# ThreePhaseMLI.net
KiCad netlist of a schematic drawn in Altium Designer
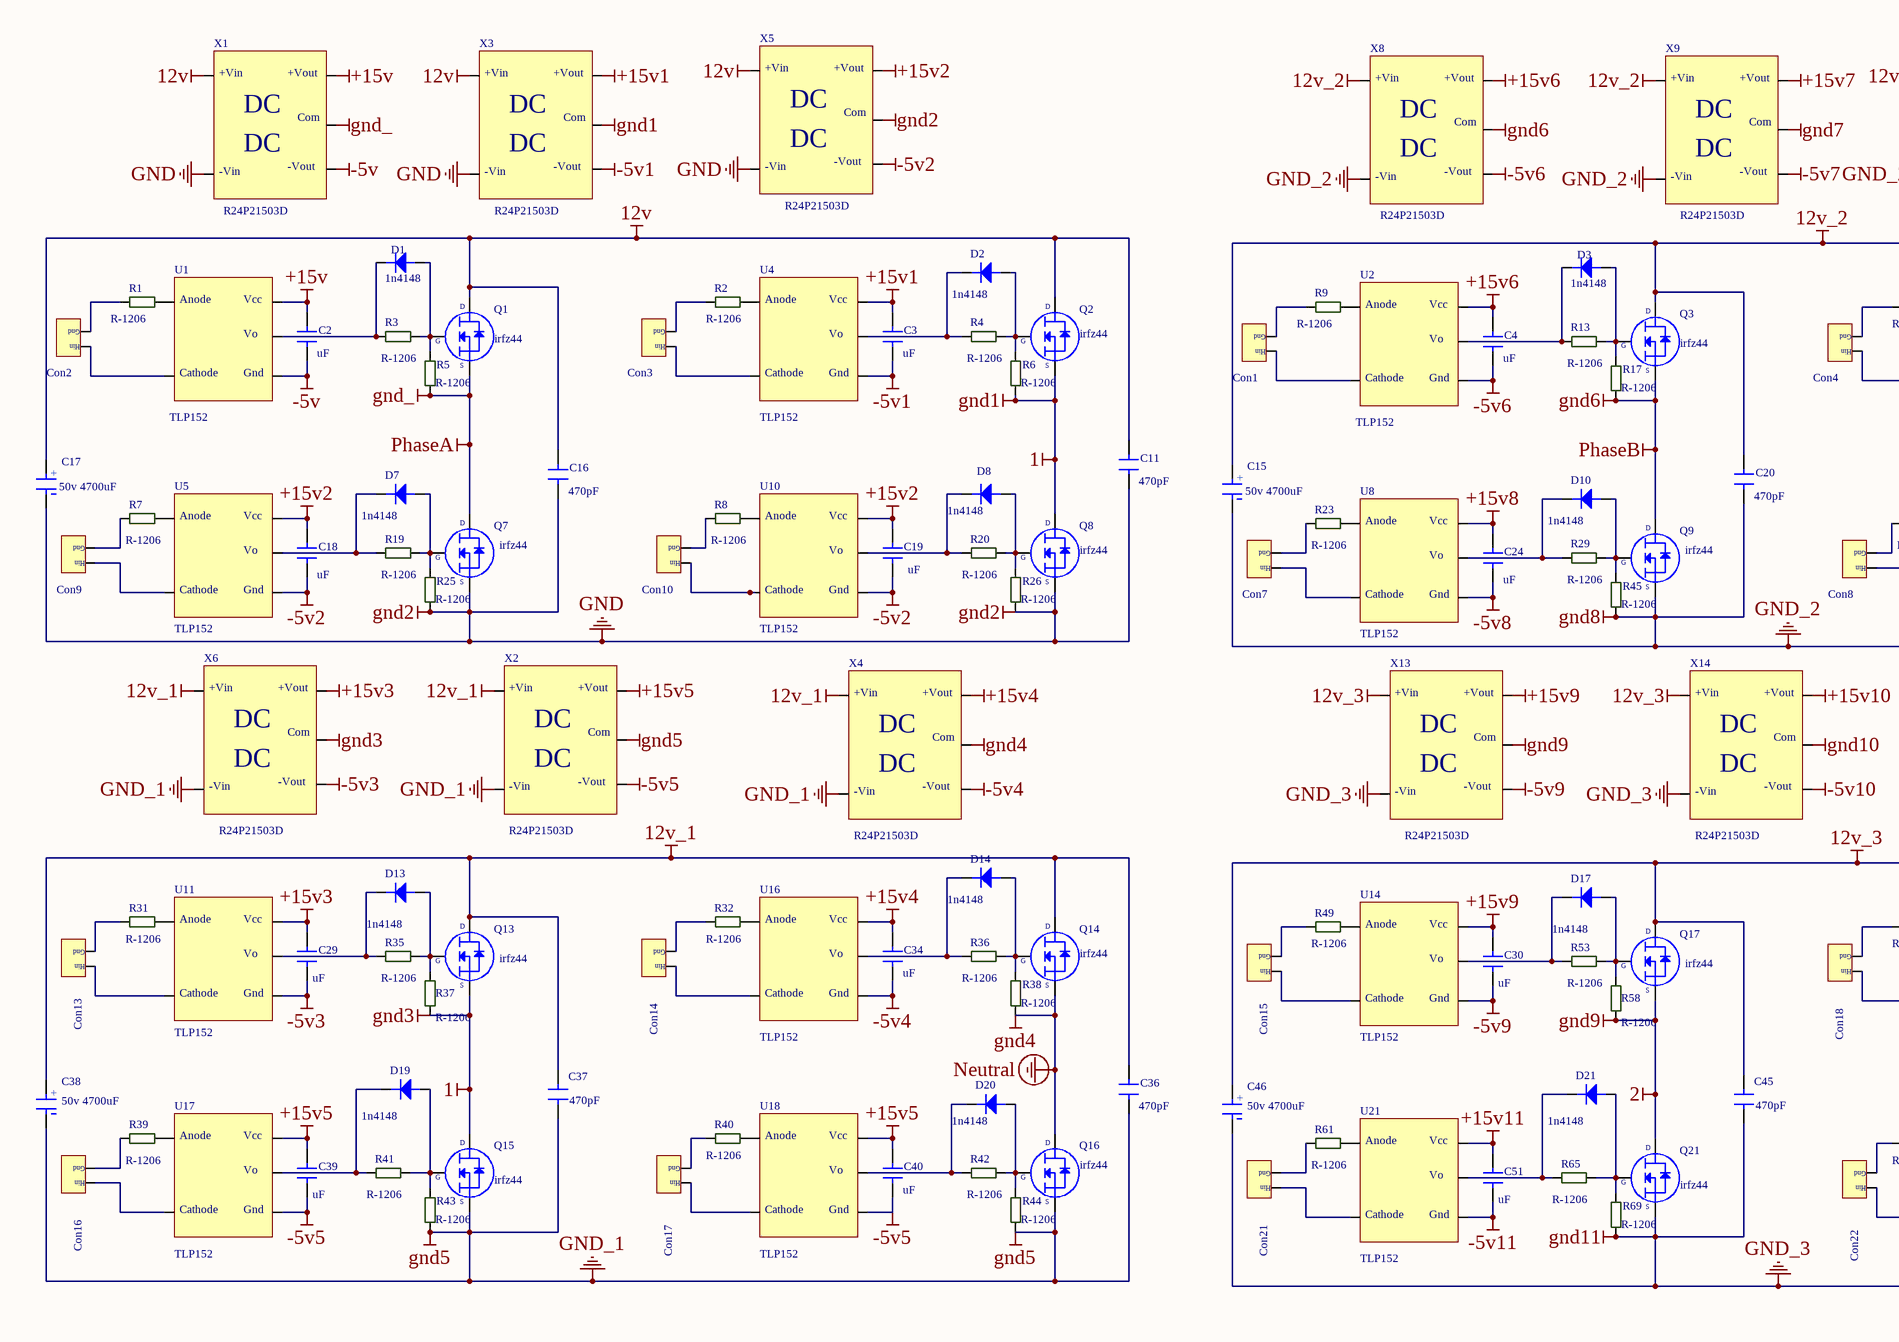
[diagram p0: ThreePhaseMLI.SchDoc, left]
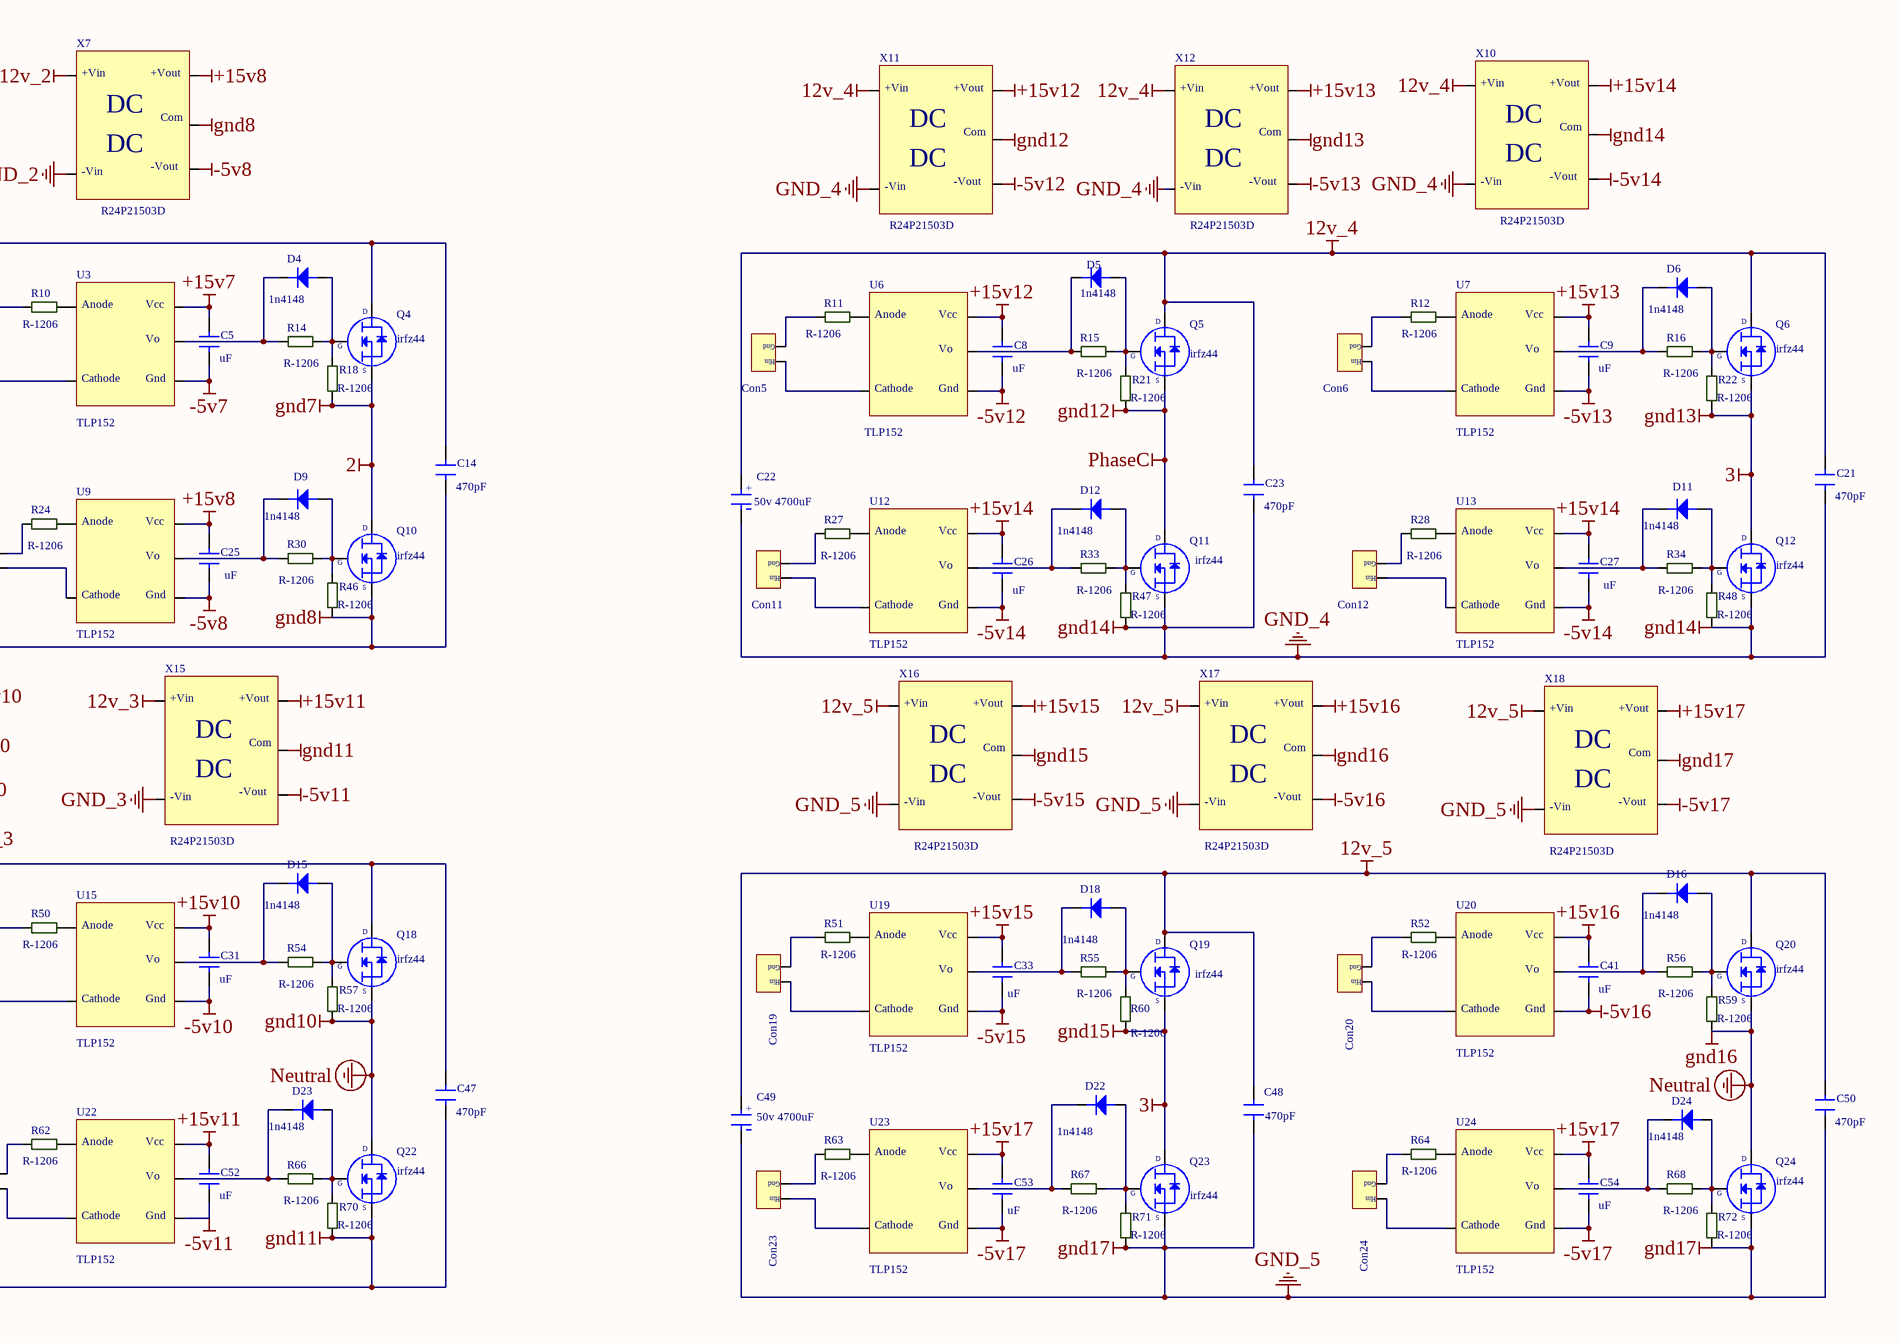
[diagram p1: ThreePhaseMLI.SchDoc, right]

(export (version "E")
  (design (tool "Eeschema 10.0.6"))
  (components
    (comp (ref "C2") (value "uF") (footprint "C-1206") (libsource (lib "ThreePhaseMLI") (part "C-1206")))
    (comp (ref "C3") (value "uF") (footprint "C-1206") (libsource (lib "ThreePhaseMLI") (part "C-1206")))
    (comp (ref "C4") (value "uF") (footprint "C-1206") (libsource (lib "ThreePhaseMLI") (part "C-1206")))
    (comp (ref "C5") (value "uF") (footprint "C-1206") (libsource (lib "ThreePhaseMLI") (part "C-1206")))
    (comp (ref "C8") (value "uF") (footprint "C-1206") (libsource (lib "ThreePhaseMLI") (part "C-1206")))
    (comp (ref "C9") (value "uF") (footprint "C-1206") (libsource (lib "ThreePhaseMLI") (part "C-1206")))
    (comp (ref "C11")
      (value "470pF")
      (footprint "100v 470pF")
      (libsource (lib "ThreePhaseMLI") (part "100v 470p cap"))
    )
    (comp (ref "C14")
      (value "470pF")
      (footprint "100v 470pF")
      (libsource (lib "ThreePhaseMLI") (part "100v 470p cap"))
    )
    (comp (ref "C15")
      (value "50v 4700uF")
      (footprint "63v 2200uF")
      (description "PKL5-063V472MM450 Aluminum Electrolytic Capacitors - Snap In 63volts 4700uF 20%")
      (fields
        (field (name "MANUFACTURER") "Nichicon")
        (field (name "MANUFACTURER PART NUMBER") "LKS1J472MESZ")
      )
      (libsource (lib "ThreePhaseMLI") (part "Aluminum Electrolytic Capacitors"))
    )
    (comp (ref "C16")
      (value "470pF")
      (footprint "100v 470pF")
      (libsource (lib "ThreePhaseMLI") (part "100v 470p cap"))
    )
    (comp (ref "C17")
      (value "50v 4700uF")
      (footprint "63v 2200uF")
      (description "PKL5-063V472MM450 Aluminum Electrolytic Capacitors - Snap In 63volts 4700uF 20%")
      (fields
        (field (name "MANUFACTURER") "Nichicon")
        (field (name "MANUFACTURER PART NUMBER") "LKS1J472MESZ")
      )
      (libsource (lib "ThreePhaseMLI") (part "Aluminum Electrolytic Capacitors"))
    )
    (comp (ref "C18") (value "uF") (footprint "C-1206") (libsource (lib "ThreePhaseMLI") (part "C-1206")))
    (comp (ref "C19") (value "uF") (footprint "C-1206") (libsource (lib "ThreePhaseMLI") (part "C-1206")))
    (comp (ref "C20")
      (value "470pF")
      (footprint "100v 470pF")
      (libsource (lib "ThreePhaseMLI") (part "100v 470p cap"))
    )
    (comp (ref "C21")
      (value "470pF")
      (footprint "100v 470pF")
      (libsource (lib "ThreePhaseMLI") (part "100v 470p cap"))
    )
    (comp (ref "C22")
      (value "50v 4700uF")
      (footprint "63v 2200uF")
      (description "PKL5-063V472MM450 Aluminum Electrolytic Capacitors - Snap In 63volts 4700uF 20%")
      (fields
        (field (name "MANUFACTURER") "Nichicon")
        (field (name "MANUFACTURER PART NUMBER") "LKS1J472MESZ")
      )
      (libsource (lib "ThreePhaseMLI") (part "Aluminum Electrolytic Capacitors"))
    )
    (comp (ref "C23")
      (value "470pF")
      (footprint "100v 470pF")
      (libsource (lib "ThreePhaseMLI") (part "100v 470p cap"))
    )
    (comp (ref "C24") (value "uF") (footprint "C-1206") (libsource (lib "ThreePhaseMLI") (part "C-1206")))
    (comp (ref "C25") (value "uF") (footprint "C-1206") (libsource (lib "ThreePhaseMLI") (part "C-1206")))
    (comp (ref "C26") (value "uF") (footprint "C-1206") (libsource (lib "ThreePhaseMLI") (part "C-1206")))
    (comp (ref "C27") (value "uF") (footprint "C-1206") (libsource (lib "ThreePhaseMLI") (part "C-1206")))
    (comp (ref "C29") (value "uF") (footprint "C-1206") (libsource (lib "ThreePhaseMLI") (part "C-1206")))
    (comp (ref "C30") (value "uF") (footprint "C-1206") (libsource (lib "ThreePhaseMLI") (part "C-1206")))
    (comp (ref "C31") (value "uF") (footprint "C-1206") (libsource (lib "ThreePhaseMLI") (part "C-1206")))
    (comp (ref "C33") (value "uF") (footprint "C-1206") (libsource (lib "ThreePhaseMLI") (part "C-1206")))
    (comp (ref "C34") (value "uF") (footprint "C-1206") (libsource (lib "ThreePhaseMLI") (part "C-1206")))
    (comp (ref "C36")
      (value "470pF")
      (footprint "100v 470pF")
      (libsource (lib "ThreePhaseMLI") (part "100v 470p cap"))
    )
    (comp (ref "C37")
      (value "470pF")
      (footprint "100v 470pF")
      (libsource (lib "ThreePhaseMLI") (part "100v 470p cap"))
    )
    (comp (ref "C38")
      (value "50v 4700uF")
      (footprint "63v 2200uF")
      (description "PKL5-063V472MM450 Aluminum Electrolytic Capacitors - Snap In 63volts 4700uF 20%")
      (fields
        (field (name "MANUFACTURER") "Nichicon")
        (field (name "MANUFACTURER PART NUMBER") "LKS1J472MESZ")
      )
      (libsource (lib "ThreePhaseMLI") (part "Aluminum Electrolytic Capacitors"))
    )
    (comp (ref "C39") (value "uF") (footprint "C-1206") (libsource (lib "ThreePhaseMLI") (part "C-1206")))
    (comp (ref "C40") (value "uF") (footprint "C-1206") (libsource (lib "ThreePhaseMLI") (part "C-1206")))
    (comp (ref "C41") (value "uF") (footprint "C-1206") (libsource (lib "ThreePhaseMLI") (part "C-1206")))
    (comp (ref "C45")
      (value "470pF")
      (footprint "100v 470pF")
      (libsource (lib "ThreePhaseMLI") (part "100v 470p cap"))
    )
    (comp (ref "C46")
      (value "50v 4700uF")
      (footprint "63v 2200uF")
      (description "PKL5-063V472MM450 Aluminum Electrolytic Capacitors - Snap In 63volts 4700uF 20%")
      (fields
        (field (name "MANUFACTURER") "Nichicon")
        (field (name "MANUFACTURER PART NUMBER") "LKS1J472MESZ")
      )
      (libsource (lib "ThreePhaseMLI") (part "Aluminum Electrolytic Capacitors"))
    )
    (comp (ref "C47")
      (value "470pF")
      (footprint "100v 470pF")
      (libsource (lib "ThreePhaseMLI") (part "100v 470p cap"))
    )
    (comp (ref "C48")
      (value "470pF")
      (footprint "100v 470pF")
      (libsource (lib "ThreePhaseMLI") (part "100v 470p cap"))
    )
    (comp (ref "C49")
      (value "50v 4700uF")
      (footprint "63v 2200uF")
      (description "PKL5-063V472MM450 Aluminum Electrolytic Capacitors - Snap In 63volts 4700uF 20%")
      (fields
        (field (name "MANUFACTURER") "Nichicon")
        (field (name "MANUFACTURER PART NUMBER") "LKS1J472MESZ")
      )
      (libsource (lib "ThreePhaseMLI") (part "Aluminum Electrolytic Capacitors"))
    )
    (comp (ref "C50")
      (value "470pF")
      (footprint "100v 470pF")
      (libsource (lib "ThreePhaseMLI") (part "100v 470p cap"))
    )
    (comp (ref "C51") (value "uF") (footprint "C-1206") (libsource (lib "ThreePhaseMLI") (part "C-1206")))
    (comp (ref "C52") (value "uF") (footprint "C-1206") (libsource (lib "ThreePhaseMLI") (part "C-1206")))
    (comp (ref "C53") (value "uF") (footprint "C-1206") (libsource (lib "ThreePhaseMLI") (part "C-1206")))
    (comp (ref "C54") (value "uF") (footprint "C-1206") (libsource (lib "ThreePhaseMLI") (part "C-1206")))
    (comp (ref "Con1")
      (value "Connector2")
      (footprint "Conn")
      (libsource (lib "ThreePhaseMLI") (part "Connector2"))
    )
    (comp (ref "Con2")
      (value "Connector2")
      (footprint "Conn")
      (libsource (lib "ThreePhaseMLI") (part "Connector2"))
    )
    (comp (ref "Con3")
      (value "Connector2")
      (footprint "Conn")
      (libsource (lib "ThreePhaseMLI") (part "Connector2"))
    )
    (comp (ref "Con4")
      (value "Connector2")
      (footprint "Conn")
      (libsource (lib "ThreePhaseMLI") (part "Connector2"))
    )
    (comp (ref "Con5")
      (value "Connector2")
      (footprint "Conn")
      (libsource (lib "ThreePhaseMLI") (part "Connector2"))
    )
    (comp (ref "Con6")
      (value "Connector2")
      (footprint "Conn")
      (libsource (lib "ThreePhaseMLI") (part "Connector2"))
    )
    (comp (ref "Con7")
      (value "Connector2")
      (footprint "Conn")
      (libsource (lib "ThreePhaseMLI") (part "Connector2"))
    )
    (comp (ref "Con8")
      (value "Connector2")
      (footprint "Conn")
      (libsource (lib "ThreePhaseMLI") (part "Connector2"))
    )
    (comp (ref "Con9")
      (value "Connector2")
      (footprint "Conn")
      (libsource (lib "ThreePhaseMLI") (part "Connector2"))
    )
    (comp (ref "Con10")
      (value "Connector2")
      (footprint "Conn")
      (libsource (lib "ThreePhaseMLI") (part "Connector2"))
    )
    (comp (ref "Con11")
      (value "Connector2")
      (footprint "Conn")
      (libsource (lib "ThreePhaseMLI") (part "Connector2"))
    )
    (comp (ref "Con12")
      (value "Connector2")
      (footprint "Conn")
      (libsource (lib "ThreePhaseMLI") (part "Connector2"))
    )
    (comp (ref "Con13")
      (value "Connector2")
      (footprint "Conn")
      (libsource (lib "ThreePhaseMLI") (part "Connector2"))
    )
    (comp (ref "Con14")
      (value "Connector2")
      (footprint "Conn")
      (libsource (lib "ThreePhaseMLI") (part "Connector2"))
    )
    (comp (ref "Con15")
      (value "Connector2")
      (footprint "Conn")
      (libsource (lib "ThreePhaseMLI") (part "Connector2"))
    )
    (comp (ref "Con16")
      (value "Connector2")
      (footprint "Conn")
      (libsource (lib "ThreePhaseMLI") (part "Connector2"))
    )
    (comp (ref "Con17")
      (value "Connector2")
      (footprint "Conn")
      (libsource (lib "ThreePhaseMLI") (part "Connector2"))
    )
    (comp (ref "Con18")
      (value "Connector2")
      (footprint "Conn")
      (libsource (lib "ThreePhaseMLI") (part "Connector2"))
    )
    (comp (ref "Con19")
      (value "Connector2")
      (footprint "Conn")
      (libsource (lib "ThreePhaseMLI") (part "Connector2"))
    )
    (comp (ref "Con20")
      (value "Connector2")
      (footprint "Conn")
      (libsource (lib "ThreePhaseMLI") (part "Connector2"))
    )
    (comp (ref "Con21")
      (value "Connector2")
      (footprint "Conn")
      (libsource (lib "ThreePhaseMLI") (part "Connector2"))
    )
    (comp (ref "Con22")
      (value "Connector2")
      (footprint "Conn")
      (libsource (lib "ThreePhaseMLI") (part "Connector2"))
    )
    (comp (ref "Con23")
      (value "Connector2")
      (footprint "Conn")
      (libsource (lib "ThreePhaseMLI") (part "Connector2"))
    )
    (comp (ref "Con24")
      (value "Connector2")
      (footprint "Conn")
      (libsource (lib "ThreePhaseMLI") (part "Connector2"))
    )
    (comp (ref "D1")
      (value "1n4148")
      (footprint "B5819")
      (description "Diode Small Signal Switching 100V 0.15A 2-Pin SOD-123 T/R")
      (fields
        (field (name "MANUFACTURER") "Vishay")
        (field (name "MANUFACTURER PART NUMBER") "1N4148W-E3-18")
      )
      (libsource (lib "ThreePhaseMLI") (part "1N4148W-E3-18"))
    )
    (comp (ref "D2")
      (value "1n4148")
      (footprint "B5819")
      (description "Diode Small Signal Switching 100V 0.15A 2-Pin SOD-123 T/R")
      (fields
        (field (name "MANUFACTURER") "Vishay")
        (field (name "MANUFACTURER PART NUMBER") "1N4148W-E3-18")
      )
      (libsource (lib "ThreePhaseMLI") (part "1N4148W-E3-18"))
    )
    (comp (ref "D3")
      (value "1n4148")
      (footprint "B5819")
      (description "Diode Small Signal Switching 100V 0.15A 2-Pin SOD-123 T/R")
      (fields
        (field (name "MANUFACTURER") "Vishay")
        (field (name "MANUFACTURER PART NUMBER") "1N4148W-E3-18")
      )
      (libsource (lib "ThreePhaseMLI") (part "1N4148W-E3-18"))
    )
    (comp (ref "D4")
      (value "1n4148")
      (footprint "B5819")
      (description "Diode Small Signal Switching 100V 0.15A 2-Pin SOD-123 T/R")
      (fields
        (field (name "MANUFACTURER") "Vishay")
        (field (name "MANUFACTURER PART NUMBER") "1N4148W-E3-18")
      )
      (libsource (lib "ThreePhaseMLI") (part "1N4148W-E3-18"))
    )
    (comp (ref "D5")
      (value "1n4148")
      (footprint "B5819")
      (description "Diode Small Signal Switching 100V 0.15A 2-Pin SOD-123 T/R")
      (fields
        (field (name "MANUFACTURER") "Vishay")
        (field (name "MANUFACTURER PART NUMBER") "1N4148W-E3-18")
      )
      (libsource (lib "ThreePhaseMLI") (part "1N4148W-E3-18"))
    )
    (comp (ref "D6")
      (value "1n4148")
      (footprint "B5819")
      (description "Diode Small Signal Switching 100V 0.15A 2-Pin SOD-123 T/R")
      (fields
        (field (name "MANUFACTURER") "Vishay")
        (field (name "MANUFACTURER PART NUMBER") "1N4148W-E3-18")
      )
      (libsource (lib "ThreePhaseMLI") (part "1N4148W-E3-18"))
    )
    (comp (ref "D7")
      (value "1n4148")
      (footprint "B5819")
      (description "Diode Small Signal Switching 100V 0.15A 2-Pin SOD-123 T/R")
      (fields
        (field (name "MANUFACTURER") "Vishay")
        (field (name "MANUFACTURER PART NUMBER") "1N4148W-E3-18")
      )
      (libsource (lib "ThreePhaseMLI") (part "1N4148W-E3-18"))
    )
    (comp (ref "D8")
      (value "1n4148")
      (footprint "B5819")
      (description "Diode Small Signal Switching 100V 0.15A 2-Pin SOD-123 T/R")
      (fields
        (field (name "MANUFACTURER") "Vishay")
        (field (name "MANUFACTURER PART NUMBER") "1N4148W-E3-18")
      )
      (libsource (lib "ThreePhaseMLI") (part "1N4148W-E3-18"))
    )
    (comp (ref "D9")
      (value "1n4148")
      (footprint "B5819")
      (description "Diode Small Signal Switching 100V 0.15A 2-Pin SOD-123 T/R")
      (fields
        (field (name "MANUFACTURER") "Vishay")
        (field (name "MANUFACTURER PART NUMBER") "1N4148W-E3-18")
      )
      (libsource (lib "ThreePhaseMLI") (part "1N4148W-E3-18"))
    )
    (comp (ref "D10")
      (value "1n4148")
      (footprint "B5819")
      (description "Diode Small Signal Switching 100V 0.15A 2-Pin SOD-123 T/R")
      (fields
        (field (name "MANUFACTURER") "Vishay")
        (field (name "MANUFACTURER PART NUMBER") "1N4148W-E3-18")
      )
      (libsource (lib "ThreePhaseMLI") (part "1N4148W-E3-18"))
    )
    (comp (ref "D11")
      (value "1n4148")
      (footprint "B5819")
      (description "Diode Small Signal Switching 100V 0.15A 2-Pin SOD-123 T/R")
      (fields
        (field (name "MANUFACTURER") "Vishay")
        (field (name "MANUFACTURER PART NUMBER") "1N4148W-E3-18")
      )
      (libsource (lib "ThreePhaseMLI") (part "1N4148W-E3-18"))
    )
    (comp (ref "D12")
      (value "1n4148")
      (footprint "B5819")
      (description "Diode Small Signal Switching 100V 0.15A 2-Pin SOD-123 T/R")
      (fields
        (field (name "MANUFACTURER") "Vishay")
        (field (name "MANUFACTURER PART NUMBER") "1N4148W-E3-18")
      )
      (libsource (lib "ThreePhaseMLI") (part "1N4148W-E3-18"))
    )
    (comp (ref "D13")
      (value "1n4148")
      (footprint "B5819")
      (description "Diode Small Signal Switching 100V 0.15A 2-Pin SOD-123 T/R")
      (fields
        (field (name "MANUFACTURER") "Vishay")
        (field (name "MANUFACTURER PART NUMBER") "1N4148W-E3-18")
      )
      (libsource (lib "ThreePhaseMLI") (part "1N4148W-E3-18"))
    )
    (comp (ref "D14")
      (value "1n4148")
      (footprint "B5819")
      (description "Diode Small Signal Switching 100V 0.15A 2-Pin SOD-123 T/R")
      (fields
        (field (name "MANUFACTURER") "Vishay")
        (field (name "MANUFACTURER PART NUMBER") "1N4148W-E3-18")
      )
      (libsource (lib "ThreePhaseMLI") (part "1N4148W-E3-18"))
    )
    (comp (ref "D15")
      (value "1n4148")
      (footprint "B5819")
      (description "Diode Small Signal Switching 100V 0.15A 2-Pin SOD-123 T/R")
      (fields
        (field (name "MANUFACTURER") "Vishay")
        (field (name "MANUFACTURER PART NUMBER") "1N4148W-E3-18")
      )
      (libsource (lib "ThreePhaseMLI") (part "1N4148W-E3-18"))
    )
    (comp (ref "D16")
      (value "1n4148")
      (footprint "B5819")
      (description "Diode Small Signal Switching 100V 0.15A 2-Pin SOD-123 T/R")
      (fields
        (field (name "MANUFACTURER") "Vishay")
        (field (name "MANUFACTURER PART NUMBER") "1N4148W-E3-18")
      )
      (libsource (lib "ThreePhaseMLI") (part "1N4148W-E3-18"))
    )
    (comp (ref "D17")
      (value "1n4148")
      (footprint "B5819")
      (description "Diode Small Signal Switching 100V 0.15A 2-Pin SOD-123 T/R")
      (fields
        (field (name "MANUFACTURER") "Vishay")
        (field (name "MANUFACTURER PART NUMBER") "1N4148W-E3-18")
      )
      (libsource (lib "ThreePhaseMLI") (part "1N4148W-E3-18"))
    )
    (comp (ref "D18")
      (value "1n4148")
      (footprint "B5819")
      (description "Diode Small Signal Switching 100V 0.15A 2-Pin SOD-123 T/R")
      (fields
        (field (name "MANUFACTURER") "Vishay")
        (field (name "MANUFACTURER PART NUMBER") "1N4148W-E3-18")
      )
      (libsource (lib "ThreePhaseMLI") (part "1N4148W-E3-18"))
    )
    (comp (ref "D19")
      (value "1n4148")
      (footprint "B5819")
      (description "Diode Small Signal Switching 100V 0.15A 2-Pin SOD-123 T/R")
      (fields
        (field (name "MANUFACTURER") "Vishay")
        (field (name "MANUFACTURER PART NUMBER") "1N4148W-E3-18")
      )
      (libsource (lib "ThreePhaseMLI") (part "1N4148W-E3-18"))
    )
    (comp (ref "D20")
      (value "1n4148")
      (footprint "B5819")
      (description "Diode Small Signal Switching 100V 0.15A 2-Pin SOD-123 T/R")
      (fields
        (field (name "MANUFACTURER") "Vishay")
        (field (name "MANUFACTURER PART NUMBER") "1N4148W-E3-18")
      )
      (libsource (lib "ThreePhaseMLI") (part "1N4148W-E3-18"))
    )
    (comp (ref "D21")
      (value "1n4148")
      (footprint "B5819")
      (description "Diode Small Signal Switching 100V 0.15A 2-Pin SOD-123 T/R")
      (fields
        (field (name "MANUFACTURER") "Vishay")
        (field (name "MANUFACTURER PART NUMBER") "1N4148W-E3-18")
      )
      (libsource (lib "ThreePhaseMLI") (part "1N4148W-E3-18"))
    )
    (comp (ref "D22")
      (value "1n4148")
      (footprint "B5819")
      (description "Diode Small Signal Switching 100V 0.15A 2-Pin SOD-123 T/R")
      (fields
        (field (name "MANUFACTURER") "Vishay")
        (field (name "MANUFACTURER PART NUMBER") "1N4148W-E3-18")
      )
      (libsource (lib "ThreePhaseMLI") (part "1N4148W-E3-18"))
    )
    (comp (ref "D23")
      (value "1n4148")
      (footprint "B5819")
      (description "Diode Small Signal Switching 100V 0.15A 2-Pin SOD-123 T/R")
      (fields
        (field (name "MANUFACTURER") "Vishay")
        (field (name "MANUFACTURER PART NUMBER") "1N4148W-E3-18")
      )
      (libsource (lib "ThreePhaseMLI") (part "1N4148W-E3-18"))
    )
    (comp (ref "D24")
      (value "1n4148")
      (footprint "B5819")
      (description "Diode Small Signal Switching 100V 0.15A 2-Pin SOD-123 T/R")
      (fields
        (field (name "MANUFACTURER") "Vishay")
        (field (name "MANUFACTURER PART NUMBER") "1N4148W-E3-18")
      )
      (libsource (lib "ThreePhaseMLI") (part "1N4148W-E3-18"))
    )
    (comp (ref "Q1")
      (value "irfz44")
      (footprint "DPAK_TO263")
      (libsource (lib "ThreePhaseMLI") (part "To220 Mosfet"))
    )
    (comp (ref "Q2")
      (value "irfz44")
      (footprint "DPAK_TO263")
      (libsource (lib "ThreePhaseMLI") (part "To220 Mosfet"))
    )
    (comp (ref "Q3")
      (value "irfz44")
      (footprint "DPAK_TO263")
      (libsource (lib "ThreePhaseMLI") (part "To220 Mosfet"))
    )
    (comp (ref "Q4")
      (value "irfz44")
      (footprint "DPAK_TO263")
      (libsource (lib "ThreePhaseMLI") (part "To220 Mosfet"))
    )
    (comp (ref "Q5")
      (value "irfz44")
      (footprint "DPAK_TO263")
      (libsource (lib "ThreePhaseMLI") (part "To220 Mosfet"))
    )
    (comp (ref "Q6")
      (value "irfz44")
      (footprint "DPAK_TO263")
      (libsource (lib "ThreePhaseMLI") (part "To220 Mosfet"))
    )
    (comp (ref "Q7")
      (value "irfz44")
      (footprint "DPAK_TO263")
      (libsource (lib "ThreePhaseMLI") (part "To220 Mosfet"))
    )
    (comp (ref "Q8")
      (value "irfz44")
      (footprint "DPAK_TO263")
      (libsource (lib "ThreePhaseMLI") (part "To220 Mosfet"))
    )
    (comp (ref "Q9")
      (value "irfz44")
      (footprint "DPAK_TO263")
      (libsource (lib "ThreePhaseMLI") (part "To220 Mosfet"))
    )
    (comp (ref "Q10")
      (value "irfz44")
      (footprint "DPAK_TO263")
      (libsource (lib "ThreePhaseMLI") (part "To220 Mosfet"))
    )
    (comp (ref "Q11")
      (value "irfz44")
      (footprint "DPAK_TO263")
      (libsource (lib "ThreePhaseMLI") (part "To220 Mosfet"))
    )
    (comp (ref "Q12")
      (value "irfz44")
      (footprint "DPAK_TO263")
      (libsource (lib "ThreePhaseMLI") (part "To220 Mosfet"))
    )
    (comp (ref "Q13")
      (value "irfz44")
      (footprint "DPAK_TO263")
      (libsource (lib "ThreePhaseMLI") (part "To220 Mosfet"))
    )
    (comp (ref "Q14")
      (value "irfz44")
      (footprint "DPAK_TO263")
      (libsource (lib "ThreePhaseMLI") (part "To220 Mosfet"))
    )
    (comp (ref "Q15")
      (value "irfz44")
      (footprint "DPAK_TO263")
      (libsource (lib "ThreePhaseMLI") (part "To220 Mosfet"))
    )
    (comp (ref "Q16")
      (value "irfz44")
      (footprint "DPAK_TO263")
      (libsource (lib "ThreePhaseMLI") (part "To220 Mosfet"))
    )
    (comp (ref "Q17")
      (value "irfz44")
      (footprint "DPAK_TO263")
      (libsource (lib "ThreePhaseMLI") (part "To220 Mosfet"))
    )
    (comp (ref "Q18")
      (value "irfz44")
      (footprint "DPAK_TO263")
      (libsource (lib "ThreePhaseMLI") (part "To220 Mosfet"))
    )
    (comp (ref "Q19")
      (value "irfz44")
      (footprint "DPAK_TO263")
      (libsource (lib "ThreePhaseMLI") (part "To220 Mosfet"))
    )
    (comp (ref "Q20")
      (value "irfz44")
      (footprint "DPAK_TO263")
      (libsource (lib "ThreePhaseMLI") (part "To220 Mosfet"))
    )
    (comp (ref "Q21")
      (value "irfz44")
      (footprint "DPAK_TO263")
      (libsource (lib "ThreePhaseMLI") (part "To220 Mosfet"))
    )
    (comp (ref "Q22")
      (value "irfz44")
      (footprint "DPAK_TO263")
      (libsource (lib "ThreePhaseMLI") (part "To220 Mosfet"))
    )
    (comp (ref "Q23")
      (value "irfz44")
      (footprint "DPAK_TO263")
      (libsource (lib "ThreePhaseMLI") (part "To220 Mosfet"))
    )
    (comp (ref "Q24")
      (value "irfz44")
      (footprint "DPAK_TO263")
      (libsource (lib "ThreePhaseMLI") (part "To220 Mosfet"))
    )
    (comp (ref "R1")
      (value "R-1206")
      (footprint "R-1206")
      (description "Res1206")
      (libsource (lib "ThreePhaseMLI") (part "R-1206"))
    )
    (comp (ref "R2")
      (value "R-1206")
      (footprint "R-1206")
      (description "Res1206")
      (libsource (lib "ThreePhaseMLI") (part "R-1206"))
    )
    (comp (ref "R3")
      (value "R-1206")
      (footprint "R-1206")
      (description "Res1206")
      (libsource (lib "ThreePhaseMLI") (part "R-1206"))
    )
    (comp (ref "R4")
      (value "R-1206")
      (footprint "R-1206")
      (description "Res1206")
      (libsource (lib "ThreePhaseMLI") (part "R-1206"))
    )
    (comp (ref "R5")
      (value "R-1206")
      (footprint "R-1206")
      (description "Res1206")
      (libsource (lib "ThreePhaseMLI") (part "R-1206"))
    )
    (comp (ref "R6")
      (value "R-1206")
      (footprint "R-1206")
      (description "Res1206")
      (libsource (lib "ThreePhaseMLI") (part "R-1206"))
    )
    (comp (ref "R7")
      (value "R-1206")
      (footprint "R-1206")
      (description "Res1206")
      (libsource (lib "ThreePhaseMLI") (part "R-1206"))
    )
    (comp (ref "R8")
      (value "R-1206")
      (footprint "R-1206")
      (description "Res1206")
      (libsource (lib "ThreePhaseMLI") (part "R-1206"))
    )
    (comp (ref "R9")
      (value "R-1206")
      (footprint "R-1206")
      (description "Res1206")
      (libsource (lib "ThreePhaseMLI") (part "R-1206"))
    )
    (comp (ref "R10")
      (value "R-1206")
      (footprint "R-1206")
      (description "Res1206")
      (libsource (lib "ThreePhaseMLI") (part "R-1206"))
    )
    (comp (ref "R11")
      (value "R-1206")
      (footprint "R-1206")
      (description "Res1206")
      (libsource (lib "ThreePhaseMLI") (part "R-1206"))
    )
    (comp (ref "R12")
      (value "R-1206")
      (footprint "R-1206")
      (description "Res1206")
      (libsource (lib "ThreePhaseMLI") (part "R-1206"))
    )
    (comp (ref "R13")
      (value "R-1206")
      (footprint "R-1206")
      (description "Res1206")
      (libsource (lib "ThreePhaseMLI") (part "R-1206"))
    )
    (comp (ref "R14")
      (value "R-1206")
      (footprint "R-1206")
      (description "Res1206")
      (libsource (lib "ThreePhaseMLI") (part "R-1206"))
    )
    (comp (ref "R15")
      (value "R-1206")
      (footprint "R-1206")
      (description "Res1206")
      (libsource (lib "ThreePhaseMLI") (part "R-1206"))
    )
    (comp (ref "R16")
      (value "R-1206")
      (footprint "R-1206")
      (description "Res1206")
      (libsource (lib "ThreePhaseMLI") (part "R-1206"))
    )
    (comp (ref "R17")
      (value "R-1206")
      (footprint "R-1206")
      (description "Res1206")
      (libsource (lib "ThreePhaseMLI") (part "R-1206"))
    )
    (comp (ref "R18")
      (value "R-1206")
      (footprint "R-1206")
      (description "Res1206")
      (libsource (lib "ThreePhaseMLI") (part "R-1206"))
    )
    (comp (ref "R19")
      (value "R-1206")
      (footprint "R-1206")
      (description "Res1206")
      (libsource (lib "ThreePhaseMLI") (part "R-1206"))
    )
    (comp (ref "R20")
      (value "R-1206")
      (footprint "R-1206")
      (description "Res1206")
      (libsource (lib "ThreePhaseMLI") (part "R-1206"))
    )
    (comp (ref "R21")
      (value "R-1206")
      (footprint "R-1206")
      (description "Res1206")
      (libsource (lib "ThreePhaseMLI") (part "R-1206"))
    )
    (comp (ref "R22")
      (value "R-1206")
      (footprint "R-1206")
      (description "Res1206")
      (libsource (lib "ThreePhaseMLI") (part "R-1206"))
    )
    (comp (ref "R23")
      (value "R-1206")
      (footprint "R-1206")
      (description "Res1206")
      (libsource (lib "ThreePhaseMLI") (part "R-1206"))
    )
    (comp (ref "R24")
      (value "R-1206")
      (footprint "R-1206")
      (description "Res1206")
      (libsource (lib "ThreePhaseMLI") (part "R-1206"))
    )
    (comp (ref "R25")
      (value "R-1206")
      (footprint "R-1206")
      (description "Res1206")
      (libsource (lib "ThreePhaseMLI") (part "R-1206"))
    )
    (comp (ref "R26")
      (value "R-1206")
      (footprint "R-1206")
      (description "Res1206")
      (libsource (lib "ThreePhaseMLI") (part "R-1206"))
    )
    (comp (ref "R27")
      (value "R-1206")
      (footprint "R-1206")
      (description "Res1206")
      (libsource (lib "ThreePhaseMLI") (part "R-1206"))
    )
    (comp (ref "R28")
      (value "R-1206")
      (footprint "R-1206")
      (description "Res1206")
      (libsource (lib "ThreePhaseMLI") (part "R-1206"))
    )
    (comp (ref "R29")
      (value "R-1206")
      (footprint "R-1206")
      (description "Res1206")
      (libsource (lib "ThreePhaseMLI") (part "R-1206"))
    )
    (comp (ref "R30")
      (value "R-1206")
      (footprint "R-1206")
      (description "Res1206")
      (libsource (lib "ThreePhaseMLI") (part "R-1206"))
    )
    (comp (ref "R31")
      (value "R-1206")
      (footprint "R-1206")
      (description "Res1206")
      (libsource (lib "ThreePhaseMLI") (part "R-1206"))
    )
    (comp (ref "R32")
      (value "R-1206")
      (footprint "R-1206")
      (description "Res1206")
      (libsource (lib "ThreePhaseMLI") (part "R-1206"))
    )
    (comp (ref "R33")
      (value "R-1206")
      (footprint "R-1206")
      (description "Res1206")
      (libsource (lib "ThreePhaseMLI") (part "R-1206"))
    )
    (comp (ref "R34")
      (value "R-1206")
      (footprint "R-1206")
      (description "Res1206")
      (libsource (lib "ThreePhaseMLI") (part "R-1206"))
    )
    (comp (ref "R35")
      (value "R-1206")
      (footprint "R-1206")
      (description "Res1206")
      (libsource (lib "ThreePhaseMLI") (part "R-1206"))
    )
    (comp (ref "R36")
      (value "R-1206")
      (footprint "R-1206")
      (description "Res1206")
      (libsource (lib "ThreePhaseMLI") (part "R-1206"))
    )
    (comp (ref "R37")
      (value "R-1206")
      (footprint "R-1206")
      (description "Res1206")
      (libsource (lib "ThreePhaseMLI") (part "R-1206"))
    )
    (comp (ref "R38")
      (value "R-1206")
      (footprint "R-1206")
      (description "Res1206")
      (libsource (lib "ThreePhaseMLI") (part "R-1206"))
    )
    (comp (ref "R39")
      (value "R-1206")
      (footprint "R-1206")
      (description "Res1206")
      (libsource (lib "ThreePhaseMLI") (part "R-1206"))
    )
    (comp (ref "R40")
      (value "R-1206")
      (footprint "R-1206")
      (description "Res1206")
      (libsource (lib "ThreePhaseMLI") (part "R-1206"))
    )
    (comp (ref "R41")
      (value "R-1206")
      (footprint "R-1206")
      (description "Res1206")
      (libsource (lib "ThreePhaseMLI") (part "R-1206"))
    )
    (comp (ref "R42")
      (value "R-1206")
      (footprint "R-1206")
      (description "Res1206")
      (libsource (lib "ThreePhaseMLI") (part "R-1206"))
    )
    (comp (ref "R43")
      (value "R-1206")
      (footprint "R-1206")
      (description "Res1206")
      (libsource (lib "ThreePhaseMLI") (part "R-1206"))
    )
    (comp (ref "R44")
      (value "R-1206")
      (footprint "R-1206")
      (description "Res1206")
      (libsource (lib "ThreePhaseMLI") (part "R-1206"))
    )
    (comp (ref "R45")
      (value "R-1206")
      (footprint "R-1206")
      (description "Res1206")
      (libsource (lib "ThreePhaseMLI") (part "R-1206"))
    )
    (comp (ref "R46")
      (value "R-1206")
      (footprint "R-1206")
      (description "Res1206")
      (libsource (lib "ThreePhaseMLI") (part "R-1206"))
    )
    (comp (ref "R47")
      (value "R-1206")
      (footprint "R-1206")
      (description "Res1206")
      (libsource (lib "ThreePhaseMLI") (part "R-1206"))
    )
    (comp (ref "R48")
      (value "R-1206")
      (footprint "R-1206")
      (description "Res1206")
      (libsource (lib "ThreePhaseMLI") (part "R-1206"))
    )
    (comp (ref "R49")
      (value "R-1206")
      (footprint "R-1206")
      (description "Res1206")
      (libsource (lib "ThreePhaseMLI") (part "R-1206"))
    )
    (comp (ref "R50")
      (value "R-1206")
      (footprint "R-1206")
      (description "Res1206")
      (libsource (lib "ThreePhaseMLI") (part "R-1206"))
    )
    (comp (ref "R51")
      (value "R-1206")
      (footprint "R-1206")
      (description "Res1206")
      (libsource (lib "ThreePhaseMLI") (part "R-1206"))
    )
    (comp (ref "R52")
      (value "R-1206")
      (footprint "R-1206")
      (description "Res1206")
      (libsource (lib "ThreePhaseMLI") (part "R-1206"))
    )
    (comp (ref "R53")
      (value "R-1206")
      (footprint "R-1206")
      (description "Res1206")
      (libsource (lib "ThreePhaseMLI") (part "R-1206"))
    )
    (comp (ref "R54")
      (value "R-1206")
      (footprint "R-1206")
      (description "Res1206")
      (libsource (lib "ThreePhaseMLI") (part "R-1206"))
    )
    (comp (ref "R55")
      (value "R-1206")
      (footprint "R-1206")
      (description "Res1206")
      (libsource (lib "ThreePhaseMLI") (part "R-1206"))
    )
    (comp (ref "R56")
      (value "R-1206")
      (footprint "R-1206")
      (description "Res1206")
      (libsource (lib "ThreePhaseMLI") (part "R-1206"))
    )
    (comp (ref "R57")
      (value "R-1206")
      (footprint "R-1206")
      (description "Res1206")
      (libsource (lib "ThreePhaseMLI") (part "R-1206"))
    )
    (comp (ref "R58")
      (value "R-1206")
      (footprint "R-1206")
      (description "Res1206")
      (libsource (lib "ThreePhaseMLI") (part "R-1206"))
    )
    (comp (ref "R59")
      (value "R-1206")
      (footprint "R-1206")
      (description "Res1206")
      (libsource (lib "ThreePhaseMLI") (part "R-1206"))
    )
    (comp (ref "R60")
      (value "R-1206")
      (footprint "R-1206")
      (description "Res1206")
      (libsource (lib "ThreePhaseMLI") (part "R-1206"))
    )
    (comp (ref "R61")
      (value "R-1206")
      (footprint "R-1206")
      (description "Res1206")
      (libsource (lib "ThreePhaseMLI") (part "R-1206"))
    )
    (comp (ref "R62")
      (value "R-1206")
      (footprint "R-1206")
      (description "Res1206")
      (libsource (lib "ThreePhaseMLI") (part "R-1206"))
    )
    (comp (ref "R63")
      (value "R-1206")
      (footprint "R-1206")
      (description "Res1206")
      (libsource (lib "ThreePhaseMLI") (part "R-1206"))
    )
    (comp (ref "R64")
      (value "R-1206")
      (footprint "R-1206")
      (description "Res1206")
      (libsource (lib "ThreePhaseMLI") (part "R-1206"))
    )
    (comp (ref "R65")
      (value "R-1206")
      (footprint "R-1206")
      (description "Res1206")
      (libsource (lib "ThreePhaseMLI") (part "R-1206"))
    )
    (comp (ref "R66")
      (value "R-1206")
      (footprint "R-1206")
      (description "Res1206")
      (libsource (lib "ThreePhaseMLI") (part "R-1206"))
    )
    (comp (ref "R67")
      (value "R-1206")
      (footprint "R-1206")
      (description "Res1206")
      (libsource (lib "ThreePhaseMLI") (part "R-1206"))
    )
    (comp (ref "R68")
      (value "R-1206")
      (footprint "R-1206")
      (description "Res1206")
      (libsource (lib "ThreePhaseMLI") (part "R-1206"))
    )
    (comp (ref "R69")
      (value "R-1206")
      (footprint "R-1206")
      (description "Res1206")
      (libsource (lib "ThreePhaseMLI") (part "R-1206"))
    )
    (comp (ref "R70")
      (value "R-1206")
      (footprint "R-1206")
      (description "Res1206")
      (libsource (lib "ThreePhaseMLI") (part "R-1206"))
    )
    (comp (ref "R71")
      (value "R-1206")
      (footprint "R-1206")
      (description "Res1206")
      (libsource (lib "ThreePhaseMLI") (part "R-1206"))
    )
    (comp (ref "R72")
      (value "R-1206")
      (footprint "R-1206")
      (description "Res1206")
      (libsource (lib "ThreePhaseMLI") (part "R-1206"))
    )
    (comp (ref "U1")
      (value "TLP152")
      (footprint "TLP152")
      (description "OPTOISO 3.75KV GATE DRIVER 6SO-5")
      (fields
        (field (name "MANUFACTURER") "Toshiba")
        (field (name "MANUFACTURER PART NUMBER") "TLP152(TPL,E")
      )
      (libsource (lib "ThreePhaseMLI") (part "TLP152(TPL,E"))
    )
    (comp (ref "U2")
      (value "TLP152")
      (footprint "TLP152")
      (description "OPTOISO 3.75KV GATE DRIVER 6SO-5")
      (fields
        (field (name "MANUFACTURER") "Toshiba")
        (field (name "MANUFACTURER PART NUMBER") "TLP152(TPL,E")
      )
      (libsource (lib "ThreePhaseMLI") (part "TLP152(TPL,E"))
    )
    (comp (ref "U3")
      (value "TLP152")
      (footprint "TLP152")
      (description "OPTOISO 3.75KV GATE DRIVER 6SO-5")
      (fields
        (field (name "MANUFACTURER") "Toshiba")
        (field (name "MANUFACTURER PART NUMBER") "TLP152(TPL,E")
      )
      (libsource (lib "ThreePhaseMLI") (part "TLP152(TPL,E"))
    )
    (comp (ref "U4")
      (value "TLP152")
      (footprint "TLP152")
      (description "OPTOISO 3.75KV GATE DRIVER 6SO-5")
      (fields
        (field (name "MANUFACTURER") "Toshiba")
        (field (name "MANUFACTURER PART NUMBER") "TLP152(TPL,E")
      )
      (libsource (lib "ThreePhaseMLI") (part "TLP152(TPL,E"))
    )
    (comp (ref "U5")
      (value "TLP152")
      (footprint "TLP152")
      (description "OPTOISO 3.75KV GATE DRIVER 6SO-5")
      (fields
        (field (name "MANUFACTURER") "Toshiba")
        (field (name "MANUFACTURER PART NUMBER") "TLP152(TPL,E")
      )
      (libsource (lib "ThreePhaseMLI") (part "TLP152(TPL,E"))
    )
    (comp (ref "U6")
      (value "TLP152")
      (footprint "TLP152")
      (description "OPTOISO 3.75KV GATE DRIVER 6SO-5")
      (fields
        (field (name "MANUFACTURER") "Toshiba")
        (field (name "MANUFACTURER PART NUMBER") "TLP152(TPL,E")
      )
      (libsource (lib "ThreePhaseMLI") (part "TLP152(TPL,E"))
    )
    (comp (ref "U7")
      (value "TLP152")
      (footprint "TLP152")
      (description "OPTOISO 3.75KV GATE DRIVER 6SO-5")
      (fields
        (field (name "MANUFACTURER") "Toshiba")
        (field (name "MANUFACTURER PART NUMBER") "TLP152(TPL,E")
      )
      (libsource (lib "ThreePhaseMLI") (part "TLP152(TPL,E"))
    )
    (comp (ref "U8")
      (value "TLP152")
      (footprint "TLP152")
      (description "OPTOISO 3.75KV GATE DRIVER 6SO-5")
      (fields
        (field (name "MANUFACTURER") "Toshiba")
        (field (name "MANUFACTURER PART NUMBER") "TLP152(TPL,E")
      )
      (libsource (lib "ThreePhaseMLI") (part "TLP152(TPL,E"))
    )
    (comp (ref "U9")
      (value "TLP152")
      (footprint "TLP152")
      (description "OPTOISO 3.75KV GATE DRIVER 6SO-5")
      (fields
        (field (name "MANUFACTURER") "Toshiba")
        (field (name "MANUFACTURER PART NUMBER") "TLP152(TPL,E")
      )
      (libsource (lib "ThreePhaseMLI") (part "TLP152(TPL,E"))
    )
    (comp (ref "U10")
      (value "TLP152")
      (footprint "TLP152")
      (description "OPTOISO 3.75KV GATE DRIVER 6SO-5")
      (fields
        (field (name "MANUFACTURER") "Toshiba")
        (field (name "MANUFACTURER PART NUMBER") "TLP152(TPL,E")
      )
      (libsource (lib "ThreePhaseMLI") (part "TLP152(TPL,E"))
    )
    (comp (ref "U11")
      (value "TLP152")
      (footprint "TLP152")
      (description "OPTOISO 3.75KV GATE DRIVER 6SO-5")
      (fields
        (field (name "MANUFACTURER") "Toshiba")
        (field (name "MANUFACTURER PART NUMBER") "TLP152(TPL,E")
      )
      (libsource (lib "ThreePhaseMLI") (part "TLP152(TPL,E"))
    )
    (comp (ref "U12")
      (value "TLP152")
      (footprint "TLP152")
      (description "OPTOISO 3.75KV GATE DRIVER 6SO-5")
      (fields
        (field (name "MANUFACTURER") "Toshiba")
        (field (name "MANUFACTURER PART NUMBER") "TLP152(TPL,E")
      )
      (libsource (lib "ThreePhaseMLI") (part "TLP152(TPL,E"))
    )
    (comp (ref "U13")
      (value "TLP152")
      (footprint "TLP152")
      (description "OPTOISO 3.75KV GATE DRIVER 6SO-5")
      (fields
        (field (name "MANUFACTURER") "Toshiba")
        (field (name "MANUFACTURER PART NUMBER") "TLP152(TPL,E")
      )
      (libsource (lib "ThreePhaseMLI") (part "TLP152(TPL,E"))
    )
    (comp (ref "U14")
      (value "TLP152")
      (footprint "TLP152")
      (description "OPTOISO 3.75KV GATE DRIVER 6SO-5")
      (fields
        (field (name "MANUFACTURER") "Toshiba")
        (field (name "MANUFACTURER PART NUMBER") "TLP152(TPL,E")
      )
      (libsource (lib "ThreePhaseMLI") (part "TLP152(TPL,E"))
    )
    (comp (ref "U15")
      (value "TLP152")
      (footprint "TLP152")
      (description "OPTOISO 3.75KV GATE DRIVER 6SO-5")
      (fields
        (field (name "MANUFACTURER") "Toshiba")
        (field (name "MANUFACTURER PART NUMBER") "TLP152(TPL,E")
      )
      (libsource (lib "ThreePhaseMLI") (part "TLP152(TPL,E"))
    )
    (comp (ref "U16")
      (value "TLP152")
      (footprint "TLP152")
      (description "OPTOISO 3.75KV GATE DRIVER 6SO-5")
      (fields
        (field (name "MANUFACTURER") "Toshiba")
        (field (name "MANUFACTURER PART NUMBER") "TLP152(TPL,E")
      )
      (libsource (lib "ThreePhaseMLI") (part "TLP152(TPL,E"))
    )
    (comp (ref "U17")
      (value "TLP152")
      (footprint "TLP152")
      (description "OPTOISO 3.75KV GATE DRIVER 6SO-5")
      (fields
        (field (name "MANUFACTURER") "Toshiba")
        (field (name "MANUFACTURER PART NUMBER") "TLP152(TPL,E")
      )
      (libsource (lib "ThreePhaseMLI") (part "TLP152(TPL,E"))
    )
    (comp (ref "U18")
      (value "TLP152")
      (footprint "TLP152")
      (description "OPTOISO 3.75KV GATE DRIVER 6SO-5")
      (fields
        (field (name "MANUFACTURER") "Toshiba")
        (field (name "MANUFACTURER PART NUMBER") "TLP152(TPL,E")
      )
      (libsource (lib "ThreePhaseMLI") (part "TLP152(TPL,E"))
    )
    (comp (ref "U19")
      (value "TLP152")
      (footprint "TLP152")
      (description "OPTOISO 3.75KV GATE DRIVER 6SO-5")
      (fields
        (field (name "MANUFACTURER") "Toshiba")
        (field (name "MANUFACTURER PART NUMBER") "TLP152(TPL,E")
      )
      (libsource (lib "ThreePhaseMLI") (part "TLP152(TPL,E"))
    )
    (comp (ref "U20")
      (value "TLP152")
      (footprint "TLP152")
      (description "OPTOISO 3.75KV GATE DRIVER 6SO-5")
      (fields
        (field (name "MANUFACTURER") "Toshiba")
        (field (name "MANUFACTURER PART NUMBER") "TLP152(TPL,E")
      )
      (libsource (lib "ThreePhaseMLI") (part "TLP152(TPL,E"))
    )
    (comp (ref "U21")
      (value "TLP152")
      (footprint "TLP152")
      (description "OPTOISO 3.75KV GATE DRIVER 6SO-5")
      (fields
        (field (name "MANUFACTURER") "Toshiba")
        (field (name "MANUFACTURER PART NUMBER") "TLP152(TPL,E")
      )
      (libsource (lib "ThreePhaseMLI") (part "TLP152(TPL,E"))
    )
    (comp (ref "U22")
      (value "TLP152")
      (footprint "TLP152")
      (description "OPTOISO 3.75KV GATE DRIVER 6SO-5")
      (fields
        (field (name "MANUFACTURER") "Toshiba")
        (field (name "MANUFACTURER PART NUMBER") "TLP152(TPL,E")
      )
      (libsource (lib "ThreePhaseMLI") (part "TLP152(TPL,E"))
    )
    (comp (ref "U23")
      (value "TLP152")
      (footprint "TLP152")
      (description "OPTOISO 3.75KV GATE DRIVER 6SO-5")
      (fields
        (field (name "MANUFACTURER") "Toshiba")
        (field (name "MANUFACTURER PART NUMBER") "TLP152(TPL,E")
      )
      (libsource (lib "ThreePhaseMLI") (part "TLP152(TPL,E"))
    )
    (comp (ref "U24")
      (value "TLP152")
      (footprint "TLP152")
      (description "OPTOISO 3.75KV GATE DRIVER 6SO-5")
      (fields
        (field (name "MANUFACTURER") "Toshiba")
        (field (name "MANUFACTURER PART NUMBER") "TLP152(TPL,E")
      )
      (libsource (lib "ThreePhaseMLI") (part "TLP152(TPL,E"))
    )
    (comp (ref "X1")
      (value "R24P21503D")
      (footprint "SIP7")
      (description "DC/DC CONV 2W 12VDC +15/-3VDC 93mA/-185mA SIP7")
      (fields (field (name "MANUFACTURER") "RECOM") (field (name "ÖZDISAN PART NUMBER") "R12P21503D"))
      (libsource (lib "ThreePhaseMLI") (part "R24P21503D"))
    )
    (comp (ref "X2")
      (value "R24P21503D")
      (footprint "SIP7")
      (description "DC/DC CONV 2W 12VDC +15/-3VDC 93mA/-185mA SIP7")
      (fields (field (name "MANUFACTURER") "RECOM") (field (name "ÖZDISAN PART NUMBER") "R12P21503D"))
      (libsource (lib "ThreePhaseMLI") (part "R24P21503D"))
    )
    (comp (ref "X3")
      (value "R24P21503D")
      (footprint "SIP7")
      (description "DC/DC CONV 2W 12VDC +15/-3VDC 93mA/-185mA SIP7")
      (fields (field (name "MANUFACTURER") "RECOM") (field (name "ÖZDISAN PART NUMBER") "R12P21503D"))
      (libsource (lib "ThreePhaseMLI") (part "R24P21503D"))
    )
    (comp (ref "X4")
      (value "R24P21503D")
      (footprint "SIP7")
      (description "DC/DC CONV 2W 12VDC +15/-3VDC 93mA/-185mA SIP7")
      (fields (field (name "MANUFACTURER") "RECOM") (field (name "ÖZDISAN PART NUMBER") "R12P21503D"))
      (libsource (lib "ThreePhaseMLI") (part "R24P21503D"))
    )
    (comp (ref "X5")
      (value "R24P21503D")
      (footprint "SIP7")
      (description "DC/DC CONV 2W 12VDC +15/-3VDC 93mA/-185mA SIP7")
      (fields (field (name "MANUFACTURER") "RECOM") (field (name "ÖZDISAN PART NUMBER") "R12P21503D"))
      (libsource (lib "ThreePhaseMLI") (part "R24P21503D"))
    )
    (comp (ref "X6")
      (value "R24P21503D")
      (footprint "SIP7")
      (description "DC/DC CONV 2W 12VDC +15/-3VDC 93mA/-185mA SIP7")
      (fields (field (name "MANUFACTURER") "RECOM") (field (name "ÖZDISAN PART NUMBER") "R12P21503D"))
      (libsource (lib "ThreePhaseMLI") (part "R24P21503D"))
    )
    (comp (ref "X7")
      (value "R24P21503D")
      (footprint "SIP7")
      (description "DC/DC CONV 2W 12VDC +15/-3VDC 93mA/-185mA SIP7")
      (fields (field (name "MANUFACTURER") "RECOM") (field (name "ÖZDISAN PART NUMBER") "R12P21503D"))
      (libsource (lib "ThreePhaseMLI") (part "R24P21503D"))
    )
    (comp (ref "X8")
      (value "R24P21503D")
      (footprint "SIP7")
      (description "DC/DC CONV 2W 12VDC +15/-3VDC 93mA/-185mA SIP7")
      (fields (field (name "MANUFACTURER") "RECOM") (field (name "ÖZDISAN PART NUMBER") "R12P21503D"))
      (libsource (lib "ThreePhaseMLI") (part "R24P21503D"))
    )
    (comp (ref "X9")
      (value "R24P21503D")
      (footprint "SIP7")
      (description "DC/DC CONV 2W 12VDC +15/-3VDC 93mA/-185mA SIP7")
      (fields (field (name "MANUFACTURER") "RECOM") (field (name "ÖZDISAN PART NUMBER") "R12P21503D"))
      (libsource (lib "ThreePhaseMLI") (part "R24P21503D"))
    )
    (comp (ref "X10")
      (value "R24P21503D")
      (footprint "SIP7")
      (description "DC/DC CONV 2W 12VDC +15/-3VDC 93mA/-185mA SIP7")
      (fields (field (name "MANUFACTURER") "RECOM") (field (name "ÖZDISAN PART NUMBER") "R12P21503D"))
      (libsource (lib "ThreePhaseMLI") (part "R24P21503D"))
    )
    (comp (ref "X11")
      (value "R24P21503D")
      (footprint "SIP7")
      (description "DC/DC CONV 2W 12VDC +15/-3VDC 93mA/-185mA SIP7")
      (fields (field (name "MANUFACTURER") "RECOM") (field (name "ÖZDISAN PART NUMBER") "R12P21503D"))
      (libsource (lib "ThreePhaseMLI") (part "R24P21503D"))
    )
    (comp (ref "X12")
      (value "R24P21503D")
      (footprint "SIP7")
      (description "DC/DC CONV 2W 12VDC +15/-3VDC 93mA/-185mA SIP7")
      (fields (field (name "MANUFACTURER") "RECOM") (field (name "ÖZDISAN PART NUMBER") "R12P21503D"))
      (libsource (lib "ThreePhaseMLI") (part "R24P21503D"))
    )
    (comp (ref "X13")
      (value "R24P21503D")
      (footprint "SIP7")
      (description "DC/DC CONV 2W 12VDC +15/-3VDC 93mA/-185mA SIP7")
      (fields (field (name "MANUFACTURER") "RECOM") (field (name "ÖZDISAN PART NUMBER") "R12P21503D"))
      (libsource (lib "ThreePhaseMLI") (part "R24P21503D"))
    )
    (comp (ref "X14")
      (value "R24P21503D")
      (footprint "SIP7")
      (description "DC/DC CONV 2W 12VDC +15/-3VDC 93mA/-185mA SIP7")
      (fields (field (name "MANUFACTURER") "RECOM") (field (name "ÖZDISAN PART NUMBER") "R12P21503D"))
      (libsource (lib "ThreePhaseMLI") (part "R24P21503D"))
    )
    (comp (ref "X15")
      (value "R24P21503D")
      (footprint "SIP7")
      (description "DC/DC CONV 2W 12VDC +15/-3VDC 93mA/-185mA SIP7")
      (fields (field (name "MANUFACTURER") "RECOM") (field (name "ÖZDISAN PART NUMBER") "R12P21503D"))
      (libsource (lib "ThreePhaseMLI") (part "R24P21503D"))
    )
    (comp (ref "X16")
      (value "R24P21503D")
      (footprint "SIP7")
      (description "DC/DC CONV 2W 12VDC +15/-3VDC 93mA/-185mA SIP7")
      (fields (field (name "MANUFACTURER") "RECOM") (field (name "ÖZDISAN PART NUMBER") "R12P21503D"))
      (libsource (lib "ThreePhaseMLI") (part "R24P21503D"))
    )
    (comp (ref "X17")
      (value "R24P21503D")
      (footprint "SIP7")
      (description "DC/DC CONV 2W 12VDC +15/-3VDC 93mA/-185mA SIP7")
      (fields (field (name "MANUFACTURER") "RECOM") (field (name "ÖZDISAN PART NUMBER") "R12P21503D"))
      (libsource (lib "ThreePhaseMLI") (part "R24P21503D"))
    )
    (comp (ref "X18")
      (value "R24P21503D")
      (footprint "SIP7")
      (description "DC/DC CONV 2W 12VDC +15/-3VDC 93mA/-185mA SIP7")
      (fields (field (name "MANUFACTURER") "RECOM") (field (name "ÖZDISAN PART NUMBER") "R12P21503D"))
      (libsource (lib "ThreePhaseMLI") (part "R24P21503D"))
    )
  )
  (nets
    (net (code "1") (name "+15v") (class "Default")
      (node (ref "C2") (pin "2") (pinfunction "2_2") (pintype "passive"))
      (node (ref "U1") (pin "5") (pinfunction "5_5") (pintype "passive"))
      (node (ref "X1") (pin "7") (pinfunction "7_7") (pintype "passive"))
    )
    (net (code "2") (name "+15v1") (class "Default")
      (node (ref "C3") (pin "2") (pinfunction "2_2") (pintype "passive"))
      (node (ref "U4") (pin "5") (pinfunction "5_5") (pintype "passive"))
      (node (ref "X3") (pin "7") (pinfunction "7_7") (pintype "passive"))
    )
    (net (code "3") (name "+15v2") (class "Default")
      (node (ref "C18") (pin "2") (pinfunction "2_2") (pintype "passive"))
      (node (ref "C19") (pin "2") (pinfunction "2_2") (pintype "passive"))
      (node (ref "U10") (pin "5") (pinfunction "5_5") (pintype "passive"))
      (node (ref "U5") (pin "5") (pinfunction "5_5") (pintype "passive"))
      (node (ref "X5") (pin "7") (pinfunction "7_7") (pintype "passive"))
    )
    (net (code "4") (name "+15v3") (class "Default")
      (node (ref "C29") (pin "2") (pinfunction "2_2") (pintype "passive"))
      (node (ref "U11") (pin "5") (pinfunction "5_5") (pintype "passive"))
      (node (ref "X6") (pin "7") (pinfunction "7_7") (pintype "passive"))
    )
    (net (code "5") (name "+15v4") (class "Default")
      (node (ref "C34") (pin "2") (pinfunction "2_2") (pintype "passive"))
      (node (ref "U16") (pin "5") (pinfunction "5_5") (pintype "passive"))
      (node (ref "X4") (pin "7") (pinfunction "7_7") (pintype "passive"))
    )
    (net (code "6") (name "+15v5") (class "Default")
      (node (ref "C39") (pin "2") (pinfunction "2_2") (pintype "passive"))
      (node (ref "C40") (pin "2") (pinfunction "2_2") (pintype "passive"))
      (node (ref "U17") (pin "5") (pinfunction "5_5") (pintype "passive"))
      (node (ref "U18") (pin "5") (pinfunction "5_5") (pintype "passive"))
      (node (ref "X2") (pin "7") (pinfunction "7_7") (pintype "passive"))
    )
    (net (code "7") (name "+15v6") (class "Default")
      (node (ref "C4") (pin "2") (pinfunction "2_2") (pintype "passive"))
      (node (ref "U2") (pin "5") (pinfunction "5_5") (pintype "passive"))
      (node (ref "X8") (pin "7") (pinfunction "7_7") (pintype "passive"))
    )
    (net (code "8") (name "+15v7") (class "Default")
      (node (ref "C5") (pin "2") (pinfunction "2_2") (pintype "passive"))
      (node (ref "U3") (pin "5") (pinfunction "5_5") (pintype "passive"))
      (node (ref "X9") (pin "7") (pinfunction "7_7") (pintype "passive"))
    )
    (net (code "9") (name "+15v8") (class "Default")
      (node (ref "C24") (pin "2") (pinfunction "2_2") (pintype "passive"))
      (node (ref "C25") (pin "2") (pinfunction "2_2") (pintype "passive"))
      (node (ref "U8") (pin "5") (pinfunction "5_5") (pintype "passive"))
      (node (ref "U9") (pin "5") (pinfunction "5_5") (pintype "passive"))
      (node (ref "X7") (pin "7") (pinfunction "7_7") (pintype "passive"))
    )
    (net (code "10") (name "+15v9") (class "Default")
      (node (ref "C30") (pin "2") (pinfunction "2_2") (pintype "passive"))
      (node (ref "U14") (pin "5") (pinfunction "5_5") (pintype "passive"))
      (node (ref "X13") (pin "7") (pinfunction "7_7") (pintype "passive"))
    )
    (net (code "11") (name "+15v10") (class "Default")
      (node (ref "C31") (pin "2") (pinfunction "2_2") (pintype "passive"))
      (node (ref "U15") (pin "5") (pinfunction "5_5") (pintype "passive"))
      (node (ref "X14") (pin "7") (pinfunction "7_7") (pintype "passive"))
    )
    (net (code "12") (name "+15v11") (class "Default")
      (node (ref "C51") (pin "2") (pinfunction "2_2") (pintype "passive"))
      (node (ref "C52") (pin "2") (pinfunction "2_2") (pintype "passive"))
      (node (ref "U21") (pin "5") (pinfunction "5_5") (pintype "passive"))
      (node (ref "U22") (pin "5") (pinfunction "5_5") (pintype "passive"))
      (node (ref "X15") (pin "7") (pinfunction "7_7") (pintype "passive"))
    )
    (net (code "13") (name "+15v12") (class "Default")
      (node (ref "C8") (pin "2") (pinfunction "2_2") (pintype "passive"))
      (node (ref "U6") (pin "5") (pinfunction "5_5") (pintype "passive"))
      (node (ref "X11") (pin "7") (pinfunction "7_7") (pintype "passive"))
    )
    (net (code "14") (name "+15v13") (class "Default")
      (node (ref "C9") (pin "2") (pinfunction "2_2") (pintype "passive"))
      (node (ref "U7") (pin "5") (pinfunction "5_5") (pintype "passive"))
      (node (ref "X12") (pin "7") (pinfunction "7_7") (pintype "passive"))
    )
    (net (code "15") (name "+15v14") (class "Default")
      (node (ref "C26") (pin "2") (pinfunction "2_2") (pintype "passive"))
      (node (ref "C27") (pin "2") (pinfunction "2_2") (pintype "passive"))
      (node (ref "U12") (pin "5") (pinfunction "5_5") (pintype "passive"))
      (node (ref "U13") (pin "5") (pinfunction "5_5") (pintype "passive"))
      (node (ref "X10") (pin "7") (pinfunction "7_7") (pintype "passive"))
    )
    (net (code "16") (name "+15v15") (class "Default")
      (node (ref "C33") (pin "2") (pinfunction "2_2") (pintype "passive"))
      (node (ref "U19") (pin "5") (pinfunction "5_5") (pintype "passive"))
      (node (ref "X16") (pin "7") (pinfunction "7_7") (pintype "passive"))
    )
    (net (code "17") (name "+15v16") (class "Default")
      (node (ref "C41") (pin "2") (pinfunction "2_2") (pintype "passive"))
      (node (ref "U20") (pin "5") (pinfunction "5_5") (pintype "passive"))
      (node (ref "X17") (pin "7") (pinfunction "7_7") (pintype "passive"))
    )
    (net (code "18") (name "+15v17") (class "Default")
      (node (ref "C53") (pin "2") (pinfunction "2_2") (pintype "passive"))
      (node (ref "C54") (pin "2") (pinfunction "2_2") (pintype "passive"))
      (node (ref "U23") (pin "5") (pinfunction "5_5") (pintype "passive"))
      (node (ref "U24") (pin "5") (pinfunction "5_5") (pintype "passive"))
      (node (ref "X18") (pin "7") (pinfunction "7_7") (pintype "passive"))
    )
    (net (code "19") (name "-5v") (class "Default")
      (node (ref "C2") (pin "1") (pinfunction "1_1") (pintype "passive"))
      (node (ref "U1") (pin "3") (pinfunction "3_3") (pintype "passive"))
      (node (ref "X1") (pin "5") (pinfunction "5_5") (pintype "passive"))
    )
    (net (code "20") (name "-5v1") (class "Default")
      (node (ref "C3") (pin "1") (pinfunction "1_1") (pintype "passive"))
      (node (ref "U4") (pin "3") (pinfunction "3_3") (pintype "passive"))
      (node (ref "X3") (pin "5") (pinfunction "5_5") (pintype "passive"))
    )
    (net (code "21") (name "-5v2") (class "Default")
      (node (ref "C18") (pin "1") (pinfunction "1_1") (pintype "passive"))
      (node (ref "C19") (pin "1") (pinfunction "1_1") (pintype "passive"))
      (node (ref "U10") (pin "3") (pinfunction "3_3") (pintype "passive"))
      (node (ref "U5") (pin "3") (pinfunction "3_3") (pintype "passive"))
      (node (ref "X5") (pin "5") (pinfunction "5_5") (pintype "passive"))
    )
    (net (code "22") (name "-5v3") (class "Default")
      (node (ref "C29") (pin "1") (pinfunction "1_1") (pintype "passive"))
      (node (ref "U11") (pin "3") (pinfunction "3_3") (pintype "passive"))
      (node (ref "X6") (pin "5") (pinfunction "5_5") (pintype "passive"))
    )
    (net (code "23") (name "-5v4") (class "Default")
      (node (ref "C34") (pin "1") (pinfunction "1_1") (pintype "passive"))
      (node (ref "U16") (pin "3") (pinfunction "3_3") (pintype "passive"))
      (node (ref "X4") (pin "5") (pinfunction "5_5") (pintype "passive"))
    )
    (net (code "24") (name "-5v5") (class "Default")
      (node (ref "C39") (pin "1") (pinfunction "1_1") (pintype "passive"))
      (node (ref "C40") (pin "1") (pinfunction "1_1") (pintype "passive"))
      (node (ref "U17") (pin "3") (pinfunction "3_3") (pintype "passive"))
      (node (ref "U18") (pin "3") (pinfunction "3_3") (pintype "passive"))
      (node (ref "X2") (pin "5") (pinfunction "5_5") (pintype "passive"))
    )
    (net (code "25") (name "-5v6") (class "Default")
      (node (ref "C4") (pin "1") (pinfunction "1_1") (pintype "passive"))
      (node (ref "U2") (pin "3") (pinfunction "3_3") (pintype "passive"))
      (node (ref "X8") (pin "5") (pinfunction "5_5") (pintype "passive"))
    )
    (net (code "26") (name "-5v7") (class "Default")
      (node (ref "C5") (pin "1") (pinfunction "1_1") (pintype "passive"))
      (node (ref "U3") (pin "3") (pinfunction "3_3") (pintype "passive"))
      (node (ref "X9") (pin "5") (pinfunction "5_5") (pintype "passive"))
    )
    (net (code "27") (name "-5v8") (class "Default")
      (node (ref "C24") (pin "1") (pinfunction "1_1") (pintype "passive"))
      (node (ref "C25") (pin "1") (pinfunction "1_1") (pintype "passive"))
      (node (ref "U8") (pin "3") (pinfunction "3_3") (pintype "passive"))
      (node (ref "U9") (pin "3") (pinfunction "3_3") (pintype "passive"))
      (node (ref "X7") (pin "5") (pinfunction "5_5") (pintype "passive"))
    )
    (net (code "28") (name "-5v9") (class "Default")
      (node (ref "C30") (pin "1") (pinfunction "1_1") (pintype "passive"))
      (node (ref "U14") (pin "3") (pinfunction "3_3") (pintype "passive"))
      (node (ref "X13") (pin "5") (pinfunction "5_5") (pintype "passive"))
    )
    (net (code "29") (name "-5v10") (class "Default")
      (node (ref "C31") (pin "1") (pinfunction "1_1") (pintype "passive"))
      (node (ref "U15") (pin "3") (pinfunction "3_3") (pintype "passive"))
      (node (ref "X14") (pin "5") (pinfunction "5_5") (pintype "passive"))
    )
    (net (code "30") (name "-5v11") (class "Default")
      (node (ref "C51") (pin "1") (pinfunction "1_1") (pintype "passive"))
      (node (ref "C52") (pin "1") (pinfunction "1_1") (pintype "passive"))
      (node (ref "U21") (pin "3") (pinfunction "3_3") (pintype "passive"))
      (node (ref "U22") (pin "3") (pinfunction "3_3") (pintype "passive"))
      (node (ref "X15") (pin "5") (pinfunction "5_5") (pintype "passive"))
    )
    (net (code "31") (name "-5v12") (class "Default")
      (node (ref "C8") (pin "1") (pinfunction "1_1") (pintype "passive"))
      (node (ref "U6") (pin "3") (pinfunction "3_3") (pintype "passive"))
      (node (ref "X11") (pin "5") (pinfunction "5_5") (pintype "passive"))
    )
    (net (code "32") (name "-5v13") (class "Default")
      (node (ref "C9") (pin "1") (pinfunction "1_1") (pintype "passive"))
      (node (ref "U7") (pin "3") (pinfunction "3_3") (pintype "passive"))
      (node (ref "X12") (pin "5") (pinfunction "5_5") (pintype "passive"))
    )
    (net (code "33") (name "-5v14") (class "Default")
      (node (ref "C26") (pin "1") (pinfunction "1_1") (pintype "passive"))
      (node (ref "C27") (pin "1") (pinfunction "1_1") (pintype "passive"))
      (node (ref "U12") (pin "3") (pinfunction "3_3") (pintype "passive"))
      (node (ref "U13") (pin "3") (pinfunction "3_3") (pintype "passive"))
      (node (ref "X10") (pin "5") (pinfunction "5_5") (pintype "passive"))
    )
    (net (code "34") (name "-5v15") (class "Default")
      (node (ref "C33") (pin "1") (pinfunction "1_1") (pintype "passive"))
      (node (ref "U19") (pin "3") (pinfunction "3_3") (pintype "passive"))
      (node (ref "X16") (pin "5") (pinfunction "5_5") (pintype "passive"))
    )
    (net (code "35") (name "-5v16") (class "Default")
      (node (ref "C41") (pin "1") (pinfunction "1_1") (pintype "passive"))
      (node (ref "U20") (pin "3") (pinfunction "3_3") (pintype "passive"))
      (node (ref "X17") (pin "5") (pinfunction "5_5") (pintype "passive"))
    )
    (net (code "36") (name "-5v17") (class "Default")
      (node (ref "C53") (pin "1") (pinfunction "1_1") (pintype "passive"))
      (node (ref "C54") (pin "1") (pinfunction "1_1") (pintype "passive"))
      (node (ref "U23") (pin "3") (pinfunction "3_3") (pintype "passive"))
      (node (ref "U24") (pin "3") (pinfunction "3_3") (pintype "passive"))
      (node (ref "X18") (pin "5") (pinfunction "5_5") (pintype "passive"))
    )
    (net (code "37") (name "1") (class "Default")
      (node (ref "Q13") (pin "3") (pinfunction "3_3") (pintype "passive"))
      (node (ref "Q15") (pin "2") (pinfunction "2_2") (pintype "passive"))
      (node (ref "Q2") (pin "3") (pinfunction "3_3") (pintype "passive"))
      (node (ref "Q8") (pin "2") (pinfunction "2_2") (pintype "passive"))
      (node (ref "R37") (pin "1") (pinfunction "1_1") (pintype "passive"))
      (node (ref "R6") (pin "1") (pinfunction "1_1") (pintype "passive"))
      (node (ref "X3") (pin "6") (pinfunction "6_6") (pintype "passive"))
      (node (ref "X6") (pin "6") (pinfunction "6_6") (pintype "passive"))
    )
    (net (code "38") (name "2") (class "Default")
      (node (ref "Q10") (pin "2") (pinfunction "2_2") (pintype "passive"))
      (node (ref "Q17") (pin "3") (pinfunction "3_3") (pintype "passive"))
      (node (ref "Q21") (pin "2") (pinfunction "2_2") (pintype "passive"))
      (node (ref "Q4") (pin "3") (pinfunction "3_3") (pintype "passive"))
      (node (ref "R18") (pin "1") (pinfunction "1_1") (pintype "passive"))
      (node (ref "R58") (pin "1") (pinfunction "1_1") (pintype "passive"))
      (node (ref "X13") (pin "6") (pinfunction "6_6") (pintype "passive"))
      (node (ref "X9") (pin "6") (pinfunction "6_6") (pintype "passive"))
    )
    (net (code "39") (name "3") (class "Default")
      (node (ref "Q12") (pin "2") (pinfunction "2_2") (pintype "passive"))
      (node (ref "Q19") (pin "3") (pinfunction "3_3") (pintype "passive"))
      (node (ref "Q23") (pin "2") (pinfunction "2_2") (pintype "passive"))
      (node (ref "Q6") (pin "3") (pinfunction "3_3") (pintype "passive"))
      (node (ref "R22") (pin "1") (pinfunction "1_1") (pintype "passive"))
      (node (ref "R60") (pin "1") (pinfunction "1_1") (pintype "passive"))
      (node (ref "X12") (pin "6") (pinfunction "6_6") (pintype "passive"))
      (node (ref "X16") (pin "6") (pinfunction "6_6") (pintype "passive"))
    )
    (net (code "40") (name "12v") (class "Default")
      (node (ref "C11") (pin "2") (pinfunction "2_2") (pintype "passive"))
      (node (ref "C16") (pin "2") (pinfunction "2_2") (pintype "passive"))
      (node (ref "C17") (pin "2") (pinfunction "2_2") (pintype "passive"))
      (node (ref "Q1") (pin "2") (pinfunction "2_2") (pintype "passive"))
      (node (ref "Q2") (pin "2") (pinfunction "2_2") (pintype "passive"))
      (node (ref "X1") (pin "1") (pinfunction "1_1") (pintype "passive"))
      (node (ref "X3") (pin "1") (pinfunction "1_1") (pintype "passive"))
      (node (ref "X5") (pin "1") (pinfunction "1_1") (pintype "passive"))
    )
    (net (code "41") (name "12v_1") (class "Default")
      (node (ref "C36") (pin "2") (pinfunction "2_2") (pintype "passive"))
      (node (ref "C37") (pin "2") (pinfunction "2_2") (pintype "passive"))
      (node (ref "C38") (pin "2") (pinfunction "2_2") (pintype "passive"))
      (node (ref "Q13") (pin "2") (pinfunction "2_2") (pintype "passive"))
      (node (ref "Q14") (pin "2") (pinfunction "2_2") (pintype "passive"))
      (node (ref "X2") (pin "1") (pinfunction "1_1") (pintype "passive"))
      (node (ref "X4") (pin "1") (pinfunction "1_1") (pintype "passive"))
      (node (ref "X6") (pin "1") (pinfunction "1_1") (pintype "passive"))
    )
    (net (code "42") (name "12v_2") (class "Default")
      (node (ref "C14") (pin "2") (pinfunction "2_2") (pintype "passive"))
      (node (ref "C15") (pin "2") (pinfunction "2_2") (pintype "passive"))
      (node (ref "C20") (pin "2") (pinfunction "2_2") (pintype "passive"))
      (node (ref "Q3") (pin "2") (pinfunction "2_2") (pintype "passive"))
      (node (ref "Q4") (pin "2") (pinfunction "2_2") (pintype "passive"))
      (node (ref "X7") (pin "1") (pinfunction "1_1") (pintype "passive"))
      (node (ref "X8") (pin "1") (pinfunction "1_1") (pintype "passive"))
      (node (ref "X9") (pin "1") (pinfunction "1_1") (pintype "passive"))
    )
    (net (code "43") (name "12v_3") (class "Default")
      (node (ref "C45") (pin "2") (pinfunction "2_2") (pintype "passive"))
      (node (ref "C46") (pin "2") (pinfunction "2_2") (pintype "passive"))
      (node (ref "C47") (pin "2") (pinfunction "2_2") (pintype "passive"))
      (node (ref "Q17") (pin "2") (pinfunction "2_2") (pintype "passive"))
      (node (ref "Q18") (pin "2") (pinfunction "2_2") (pintype "passive"))
      (node (ref "X13") (pin "1") (pinfunction "1_1") (pintype "passive"))
      (node (ref "X14") (pin "1") (pinfunction "1_1") (pintype "passive"))
      (node (ref "X15") (pin "1") (pinfunction "1_1") (pintype "passive"))
    )
    (net (code "44") (name "12v_4") (class "Default")
      (node (ref "C21") (pin "2") (pinfunction "2_2") (pintype "passive"))
      (node (ref "C22") (pin "2") (pinfunction "2_2") (pintype "passive"))
      (node (ref "C23") (pin "2") (pinfunction "2_2") (pintype "passive"))
      (node (ref "Q5") (pin "2") (pinfunction "2_2") (pintype "passive"))
      (node (ref "Q6") (pin "2") (pinfunction "2_2") (pintype "passive"))
      (node (ref "X10") (pin "1") (pinfunction "1_1") (pintype "passive"))
      (node (ref "X11") (pin "1") (pinfunction "1_1") (pintype "passive"))
      (node (ref "X12") (pin "1") (pinfunction "1_1") (pintype "passive"))
    )
    (net (code "45") (name "12v_5") (class "Default")
      (node (ref "C48") (pin "2") (pinfunction "2_2") (pintype "passive"))
      (node (ref "C49") (pin "2") (pinfunction "2_2") (pintype "passive"))
      (node (ref "C50") (pin "2") (pinfunction "2_2") (pintype "passive"))
      (node (ref "Q19") (pin "2") (pinfunction "2_2") (pintype "passive"))
      (node (ref "Q20") (pin "2") (pinfunction "2_2") (pintype "passive"))
      (node (ref "X16") (pin "1") (pinfunction "1_1") (pintype "passive"))
      (node (ref "X17") (pin "1") (pinfunction "1_1") (pintype "passive"))
      (node (ref "X18") (pin "1") (pinfunction "1_1") (pintype "passive"))
    )
    (net (code "46") (name "GND") (class "Default")
      (node (ref "C11") (pin "1") (pinfunction "1_1") (pintype "passive"))
      (node (ref "C16") (pin "1") (pinfunction "1_1") (pintype "passive"))
      (node (ref "C17") (pin "1") (pinfunction "1_1") (pintype "passive"))
      (node (ref "Q7") (pin "3") (pinfunction "3_3") (pintype "passive"))
      (node (ref "Q8") (pin "3") (pinfunction "3_3") (pintype "passive"))
      (node (ref "R25") (pin "1") (pinfunction "1_1") (pintype "passive"))
      (node (ref "R26") (pin "1") (pinfunction "1_1") (pintype "passive"))
      (node (ref "X1") (pin "2") (pinfunction "2_2") (pintype "passive"))
      (node (ref "X3") (pin "2") (pinfunction "2_2") (pintype "passive"))
      (node (ref "X5") (pin "2") (pinfunction "2_2") (pintype "passive"))
      (node (ref "X5") (pin "6") (pinfunction "6_6") (pintype "passive"))
    )
    (net (code "47") (name "GND_1") (class "Default")
      (node (ref "C36") (pin "1") (pinfunction "1_1") (pintype "passive"))
      (node (ref "C37") (pin "1") (pinfunction "1_1") (pintype "passive"))
      (node (ref "C38") (pin "1") (pinfunction "1_1") (pintype "passive"))
      (node (ref "Q15") (pin "3") (pinfunction "3_3") (pintype "passive"))
      (node (ref "Q16") (pin "3") (pinfunction "3_3") (pintype "passive"))
      (node (ref "R43") (pin "1") (pinfunction "1_1") (pintype "passive"))
      (node (ref "R44") (pin "1") (pinfunction "1_1") (pintype "passive"))
      (node (ref "X2") (pin "2") (pinfunction "2_2") (pintype "passive"))
      (node (ref "X2") (pin "6") (pinfunction "6_6") (pintype "passive"))
      (node (ref "X4") (pin "2") (pinfunction "2_2") (pintype "passive"))
      (node (ref "X6") (pin "2") (pinfunction "2_2") (pintype "passive"))
    )
    (net (code "48") (name "GND_2") (class "Default")
      (node (ref "C14") (pin "1") (pinfunction "1_1") (pintype "passive"))
      (node (ref "C15") (pin "1") (pinfunction "1_1") (pintype "passive"))
      (node (ref "C20") (pin "1") (pinfunction "1_1") (pintype "passive"))
      (node (ref "Q10") (pin "3") (pinfunction "3_3") (pintype "passive"))
      (node (ref "Q9") (pin "3") (pinfunction "3_3") (pintype "passive"))
      (node (ref "R45") (pin "1") (pinfunction "1_1") (pintype "passive"))
      (node (ref "R46") (pin "1") (pinfunction "1_1") (pintype "passive"))
      (node (ref "X7") (pin "2") (pinfunction "2_2") (pintype "passive"))
      (node (ref "X7") (pin "6") (pinfunction "6_6") (pintype "passive"))
      (node (ref "X8") (pin "2") (pinfunction "2_2") (pintype "passive"))
      (node (ref "X9") (pin "2") (pinfunction "2_2") (pintype "passive"))
    )
    (net (code "49") (name "GND_3") (class "Default")
      (node (ref "C45") (pin "1") (pinfunction "1_1") (pintype "passive"))
      (node (ref "C46") (pin "1") (pinfunction "1_1") (pintype "passive"))
      (node (ref "C47") (pin "1") (pinfunction "1_1") (pintype "passive"))
      (node (ref "Q21") (pin "3") (pinfunction "3_3") (pintype "passive"))
      (node (ref "Q22") (pin "3") (pinfunction "3_3") (pintype "passive"))
      (node (ref "R69") (pin "1") (pinfunction "1_1") (pintype "passive"))
      (node (ref "R70") (pin "1") (pinfunction "1_1") (pintype "passive"))
      (node (ref "X13") (pin "2") (pinfunction "2_2") (pintype "passive"))
      (node (ref "X14") (pin "2") (pinfunction "2_2") (pintype "passive"))
      (node (ref "X15") (pin "2") (pinfunction "2_2") (pintype "passive"))
      (node (ref "X15") (pin "6") (pinfunction "6_6") (pintype "passive"))
    )
    (net (code "50") (name "GND_4") (class "Default")
      (node (ref "C21") (pin "1") (pinfunction "1_1") (pintype "passive"))
      (node (ref "C22") (pin "1") (pinfunction "1_1") (pintype "passive"))
      (node (ref "C23") (pin "1") (pinfunction "1_1") (pintype "passive"))
      (node (ref "Q11") (pin "3") (pinfunction "3_3") (pintype "passive"))
      (node (ref "Q12") (pin "3") (pinfunction "3_3") (pintype "passive"))
      (node (ref "R47") (pin "1") (pinfunction "1_1") (pintype "passive"))
      (node (ref "R48") (pin "1") (pinfunction "1_1") (pintype "passive"))
      (node (ref "X10") (pin "2") (pinfunction "2_2") (pintype "passive"))
      (node (ref "X10") (pin "6") (pinfunction "6_6") (pintype "passive"))
      (node (ref "X11") (pin "2") (pinfunction "2_2") (pintype "passive"))
      (node (ref "X12") (pin "2") (pinfunction "2_2") (pintype "passive"))
    )
    (net (code "51") (name "GND_5") (class "Default")
      (node (ref "C48") (pin "1") (pinfunction "1_1") (pintype "passive"))
      (node (ref "C49") (pin "1") (pinfunction "1_1") (pintype "passive"))
      (node (ref "C50") (pin "1") (pinfunction "1_1") (pintype "passive"))
      (node (ref "Q23") (pin "3") (pinfunction "3_3") (pintype "passive"))
      (node (ref "Q24") (pin "3") (pinfunction "3_3") (pintype "passive"))
      (node (ref "R71") (pin "1") (pinfunction "1_1") (pintype "passive"))
      (node (ref "R72") (pin "1") (pinfunction "1_1") (pintype "passive"))
      (node (ref "X16") (pin "2") (pinfunction "2_2") (pintype "passive"))
      (node (ref "X17") (pin "2") (pinfunction "2_2") (pintype "passive"))
      (node (ref "X18") (pin "2") (pinfunction "2_2") (pintype "passive"))
      (node (ref "X18") (pin "6") (pinfunction "6_6") (pintype "passive"))
    )
    (net (code "52") (name "Net-(Con1-Pad1)") (class "Default")
      (node (ref "Con1") (pin "1") (pinfunction "1_1") (pintype "passive"))
      (node (ref "U2") (pin "2") (pinfunction "2_2") (pintype "passive"))
    )
    (net (code "53") (name "Net-(Con1-Pad2)") (class "Default")
      (node (ref "Con1") (pin "2") (pinfunction "2_2") (pintype "passive"))
      (node (ref "R9") (pin "1") (pinfunction "1_1") (pintype "passive"))
    )
    (net (code "54") (name "Net-(Con2-Pad1)") (class "Default")
      (node (ref "Con2") (pin "1") (pinfunction "1_1") (pintype "passive"))
      (node (ref "U1") (pin "2") (pinfunction "2_2") (pintype "passive"))
    )
    (net (code "55") (name "Net-(Con2-Pad2)") (class "Default")
      (node (ref "Con2") (pin "2") (pinfunction "2_2") (pintype "passive"))
      (node (ref "R1") (pin "1") (pinfunction "1_1") (pintype "passive"))
    )
    (net (code "56") (name "Net-(Con3-Pad1)") (class "Default")
      (node (ref "Con3") (pin "1") (pinfunction "1_1") (pintype "passive"))
      (node (ref "U4") (pin "2") (pinfunction "2_2") (pintype "passive"))
    )
    (net (code "57") (name "Net-(Con3-Pad2)") (class "Default")
      (node (ref "Con3") (pin "2") (pinfunction "2_2") (pintype "passive"))
      (node (ref "R2") (pin "1") (pinfunction "1_1") (pintype "passive"))
    )
    (net (code "58") (name "Net-(Con4-Pad1)") (class "Default")
      (node (ref "Con4") (pin "1") (pinfunction "1_1") (pintype "passive"))
      (node (ref "U3") (pin "2") (pinfunction "2_2") (pintype "passive"))
    )
    (net (code "59") (name "Net-(Con4-Pad2)") (class "Default")
      (node (ref "Con4") (pin "2") (pinfunction "2_2") (pintype "passive"))
      (node (ref "R10") (pin "1") (pinfunction "1_1") (pintype "passive"))
    )
    (net (code "60") (name "Net-(Con5-Pad1)") (class "Default")
      (node (ref "Con5") (pin "1") (pinfunction "1_1") (pintype "passive"))
      (node (ref "U6") (pin "2") (pinfunction "2_2") (pintype "passive"))
    )
    (net (code "61") (name "Net-(Con5-Pad2)") (class "Default")
      (node (ref "Con5") (pin "2") (pinfunction "2_2") (pintype "passive"))
      (node (ref "R11") (pin "1") (pinfunction "1_1") (pintype "passive"))
    )
    (net (code "62") (name "Net-(Con6-Pad1)") (class "Default")
      (node (ref "Con6") (pin "1") (pinfunction "1_1") (pintype "passive"))
      (node (ref "U7") (pin "2") (pinfunction "2_2") (pintype "passive"))
    )
    (net (code "63") (name "Net-(Con6-Pad2)") (class "Default")
      (node (ref "Con6") (pin "2") (pinfunction "2_2") (pintype "passive"))
      (node (ref "R12") (pin "1") (pinfunction "1_1") (pintype "passive"))
    )
    (net (code "64") (name "Net-(Con7-Pad1)") (class "Default")
      (node (ref "Con7") (pin "1") (pinfunction "1_1") (pintype "passive"))
      (node (ref "U8") (pin "2") (pinfunction "2_2") (pintype "passive"))
    )
    (net (code "65") (name "Net-(Con7-Pad2)") (class "Default")
      (node (ref "Con7") (pin "2") (pinfunction "2_2") (pintype "passive"))
      (node (ref "R23") (pin "1") (pinfunction "1_1") (pintype "passive"))
    )
    (net (code "66") (name "Net-(Con8-Pad1)") (class "Default")
      (node (ref "Con8") (pin "1") (pinfunction "1_1") (pintype "passive"))
      (node (ref "U9") (pin "2") (pinfunction "2_2") (pintype "passive"))
    )
    (net (code "67") (name "Net-(Con8-Pad2)") (class "Default")
      (node (ref "Con8") (pin "2") (pinfunction "2_2") (pintype "passive"))
      (node (ref "R24") (pin "1") (pinfunction "1_1") (pintype "passive"))
    )
    (net (code "68") (name "Net-(Con9-Pad1)") (class "Default")
      (node (ref "Con9") (pin "1") (pinfunction "1_1") (pintype "passive"))
      (node (ref "U5") (pin "2") (pinfunction "2_2") (pintype "passive"))
    )
    (net (code "69") (name "Net-(Con9-Pad2)") (class "Default")
      (node (ref "Con9") (pin "2") (pinfunction "2_2") (pintype "passive"))
      (node (ref "R7") (pin "1") (pinfunction "1_1") (pintype "passive"))
    )
    (net (code "70") (name "Net-(Con10-Pad1)") (class "Default")
      (node (ref "Con10") (pin "1") (pinfunction "1_1") (pintype "passive"))
      (node (ref "U10") (pin "2") (pinfunction "2_2") (pintype "passive"))
    )
    (net (code "71") (name "Net-(Con10-Pad2)") (class "Default")
      (node (ref "Con10") (pin "2") (pinfunction "2_2") (pintype "passive"))
      (node (ref "R8") (pin "1") (pinfunction "1_1") (pintype "passive"))
    )
    (net (code "72") (name "Net-(Con11-Pad1)") (class "Default")
      (node (ref "Con11") (pin "1") (pinfunction "1_1") (pintype "passive"))
      (node (ref "U12") (pin "2") (pinfunction "2_2") (pintype "passive"))
    )
    (net (code "73") (name "Net-(Con11-Pad2)") (class "Default")
      (node (ref "Con11") (pin "2") (pinfunction "2_2") (pintype "passive"))
      (node (ref "R27") (pin "1") (pinfunction "1_1") (pintype "passive"))
    )
    (net (code "74") (name "Net-(Con12-Pad1)") (class "Default")
      (node (ref "Con12") (pin "1") (pinfunction "1_1") (pintype "passive"))
      (node (ref "U13") (pin "2") (pinfunction "2_2") (pintype "passive"))
    )
    (net (code "75") (name "Net-(Con12-Pad2)") (class "Default")
      (node (ref "Con12") (pin "2") (pinfunction "2_2") (pintype "passive"))
      (node (ref "R28") (pin "1") (pinfunction "1_1") (pintype "passive"))
    )
    (net (code "76") (name "Net-(Con13-Pad1)") (class "Default")
      (node (ref "Con13") (pin "1") (pinfunction "1_1") (pintype "passive"))
      (node (ref "U11") (pin "2") (pinfunction "2_2") (pintype "passive"))
    )
    (net (code "77") (name "Net-(Con13-Pad2)") (class "Default")
      (node (ref "Con13") (pin "2") (pinfunction "2_2") (pintype "passive"))
      (node (ref "R31") (pin "1") (pinfunction "1_1") (pintype "passive"))
    )
    (net (code "78") (name "Net-(Con14-Pad1)") (class "Default")
      (node (ref "Con14") (pin "1") (pinfunction "1_1") (pintype "passive"))
      (node (ref "U16") (pin "2") (pinfunction "2_2") (pintype "passive"))
    )
    (net (code "79") (name "Net-(Con14-Pad2)") (class "Default")
      (node (ref "Con14") (pin "2") (pinfunction "2_2") (pintype "passive"))
      (node (ref "R32") (pin "1") (pinfunction "1_1") (pintype "passive"))
    )
    (net (code "80") (name "Net-(Con15-Pad1)") (class "Default")
      (node (ref "Con15") (pin "1") (pinfunction "1_1") (pintype "passive"))
      (node (ref "U14") (pin "2") (pinfunction "2_2") (pintype "passive"))
    )
    (net (code "81") (name "Net-(Con15-Pad2)") (class "Default")
      (node (ref "Con15") (pin "2") (pinfunction "2_2") (pintype "passive"))
      (node (ref "R49") (pin "1") (pinfunction "1_1") (pintype "passive"))
    )
    (net (code "82") (name "Net-(Con16-Pad1)") (class "Default")
      (node (ref "Con16") (pin "1") (pinfunction "1_1") (pintype "passive"))
      (node (ref "U17") (pin "2") (pinfunction "2_2") (pintype "passive"))
    )
    (net (code "83") (name "Net-(Con16-Pad2)") (class "Default")
      (node (ref "Con16") (pin "2") (pinfunction "2_2") (pintype "passive"))
      (node (ref "R39") (pin "1") (pinfunction "1_1") (pintype "passive"))
    )
    (net (code "84") (name "Net-(Con17-Pad1)") (class "Default")
      (node (ref "Con17") (pin "1") (pinfunction "1_1") (pintype "passive"))
      (node (ref "U18") (pin "2") (pinfunction "2_2") (pintype "passive"))
    )
    (net (code "85") (name "Net-(Con17-Pad2)") (class "Default")
      (node (ref "Con17") (pin "2") (pinfunction "2_2") (pintype "passive"))
      (node (ref "R40") (pin "1") (pinfunction "1_1") (pintype "passive"))
    )
    (net (code "86") (name "Net-(Con18-Pad1)") (class "Default")
      (node (ref "Con18") (pin "1") (pinfunction "1_1") (pintype "passive"))
      (node (ref "U15") (pin "2") (pinfunction "2_2") (pintype "passive"))
    )
    (net (code "87") (name "Net-(Con18-Pad2)") (class "Default")
      (node (ref "Con18") (pin "2") (pinfunction "2_2") (pintype "passive"))
      (node (ref "R50") (pin "1") (pinfunction "1_1") (pintype "passive"))
    )
    (net (code "88") (name "Net-(Con19-Pad1)") (class "Default")
      (node (ref "Con19") (pin "1") (pinfunction "1_1") (pintype "passive"))
      (node (ref "U19") (pin "2") (pinfunction "2_2") (pintype "passive"))
    )
    (net (code "89") (name "Net-(Con19-Pad2)") (class "Default")
      (node (ref "Con19") (pin "2") (pinfunction "2_2") (pintype "passive"))
      (node (ref "R51") (pin "1") (pinfunction "1_1") (pintype "passive"))
    )
    (net (code "90") (name "Net-(Con20-Pad1)") (class "Default")
      (node (ref "Con20") (pin "1") (pinfunction "1_1") (pintype "passive"))
      (node (ref "U20") (pin "2") (pinfunction "2_2") (pintype "passive"))
    )
    (net (code "91") (name "Net-(Con20-Pad2)") (class "Default")
      (node (ref "Con20") (pin "2") (pinfunction "2_2") (pintype "passive"))
      (node (ref "R52") (pin "1") (pinfunction "1_1") (pintype "passive"))
    )
    (net (code "92") (name "Net-(Con21-Pad1)") (class "Default")
      (node (ref "Con21") (pin "1") (pinfunction "1_1") (pintype "passive"))
      (node (ref "U21") (pin "2") (pinfunction "2_2") (pintype "passive"))
    )
    (net (code "93") (name "Net-(Con21-Pad2)") (class "Default")
      (node (ref "Con21") (pin "2") (pinfunction "2_2") (pintype "passive"))
      (node (ref "R61") (pin "1") (pinfunction "1_1") (pintype "passive"))
    )
    (net (code "94") (name "Net-(Con22-Pad1)") (class "Default")
      (node (ref "Con22") (pin "1") (pinfunction "1_1") (pintype "passive"))
      (node (ref "U22") (pin "2") (pinfunction "2_2") (pintype "passive"))
    )
    (net (code "95") (name "Net-(Con22-Pad2)") (class "Default")
      (node (ref "Con22") (pin "2") (pinfunction "2_2") (pintype "passive"))
      (node (ref "R62") (pin "1") (pinfunction "1_1") (pintype "passive"))
    )
    (net (code "96") (name "Net-(Con23-Pad1)") (class "Default")
      (node (ref "Con23") (pin "1") (pinfunction "1_1") (pintype "passive"))
      (node (ref "U23") (pin "2") (pinfunction "2_2") (pintype "passive"))
    )
    (net (code "97") (name "Net-(Con23-Pad2)") (class "Default")
      (node (ref "Con23") (pin "2") (pinfunction "2_2") (pintype "passive"))
      (node (ref "R63") (pin "1") (pinfunction "1_1") (pintype "passive"))
    )
    (net (code "98") (name "Net-(Con24-Pad1)") (class "Default")
      (node (ref "Con24") (pin "1") (pinfunction "1_1") (pintype "passive"))
      (node (ref "U24") (pin "2") (pinfunction "2_2") (pintype "passive"))
    )
    (net (code "99") (name "Net-(Con24-Pad2)") (class "Default")
      (node (ref "Con24") (pin "2") (pinfunction "2_2") (pintype "passive"))
      (node (ref "R64") (pin "1") (pinfunction "1_1") (pintype "passive"))
    )
    (net (code "100") (name "Net-(D1-Pad1)") (class "Default")
      (node (ref "D1") (pin "1") (pinfunction "1_1") (pintype "passive"))
      (node (ref "R3") (pin "1") (pinfunction "1_1") (pintype "passive"))
      (node (ref "U1") (pin "4") (pinfunction "4_4") (pintype "passive"))
    )
    (net (code "101") (name "Net-(D1-Pad2)") (class "Default")
      (node (ref "D1") (pin "2") (pinfunction "2_2") (pintype "passive"))
      (node (ref "Q1") (pin "1") (pinfunction "1_1") (pintype "passive"))
      (node (ref "R3") (pin "2") (pinfunction "2_2") (pintype "passive"))
      (node (ref "R5") (pin "2") (pinfunction "2_2") (pintype "passive"))
    )
    (net (code "102") (name "Net-(D2-Pad1)") (class "Default")
      (node (ref "D2") (pin "1") (pinfunction "1_1") (pintype "passive"))
      (node (ref "R4") (pin "1") (pinfunction "1_1") (pintype "passive"))
      (node (ref "U4") (pin "4") (pinfunction "4_4") (pintype "passive"))
    )
    (net (code "103") (name "Net-(D2-Pad2)") (class "Default")
      (node (ref "D2") (pin "2") (pinfunction "2_2") (pintype "passive"))
      (node (ref "Q2") (pin "1") (pinfunction "1_1") (pintype "passive"))
      (node (ref "R4") (pin "2") (pinfunction "2_2") (pintype "passive"))
      (node (ref "R6") (pin "2") (pinfunction "2_2") (pintype "passive"))
    )
    (net (code "104") (name "Net-(D3-Pad1)") (class "Default")
      (node (ref "D3") (pin "1") (pinfunction "1_1") (pintype "passive"))
      (node (ref "R13") (pin "1") (pinfunction "1_1") (pintype "passive"))
      (node (ref "U2") (pin "4") (pinfunction "4_4") (pintype "passive"))
    )
    (net (code "105") (name "Net-(D3-Pad2)") (class "Default")
      (node (ref "D3") (pin "2") (pinfunction "2_2") (pintype "passive"))
      (node (ref "Q3") (pin "1") (pinfunction "1_1") (pintype "passive"))
      (node (ref "R13") (pin "2") (pinfunction "2_2") (pintype "passive"))
      (node (ref "R17") (pin "2") (pinfunction "2_2") (pintype "passive"))
    )
    (net (code "106") (name "Net-(D4-Pad1)") (class "Default")
      (node (ref "D4") (pin "1") (pinfunction "1_1") (pintype "passive"))
      (node (ref "R14") (pin "1") (pinfunction "1_1") (pintype "passive"))
      (node (ref "U3") (pin "4") (pinfunction "4_4") (pintype "passive"))
    )
    (net (code "107") (name "Net-(D4-Pad2)") (class "Default")
      (node (ref "D4") (pin "2") (pinfunction "2_2") (pintype "passive"))
      (node (ref "Q4") (pin "1") (pinfunction "1_1") (pintype "passive"))
      (node (ref "R14") (pin "2") (pinfunction "2_2") (pintype "passive"))
      (node (ref "R18") (pin "2") (pinfunction "2_2") (pintype "passive"))
    )
    (net (code "108") (name "Net-(D5-Pad1)") (class "Default")
      (node (ref "D5") (pin "1") (pinfunction "1_1") (pintype "passive"))
      (node (ref "R15") (pin "1") (pinfunction "1_1") (pintype "passive"))
      (node (ref "U6") (pin "4") (pinfunction "4_4") (pintype "passive"))
    )
    (net (code "109") (name "Net-(D5-Pad2)") (class "Default")
      (node (ref "D5") (pin "2") (pinfunction "2_2") (pintype "passive"))
      (node (ref "Q5") (pin "1") (pinfunction "1_1") (pintype "passive"))
      (node (ref "R15") (pin "2") (pinfunction "2_2") (pintype "passive"))
      (node (ref "R21") (pin "2") (pinfunction "2_2") (pintype "passive"))
    )
    (net (code "110") (name "Net-(D6-Pad1)") (class "Default")
      (node (ref "D6") (pin "1") (pinfunction "1_1") (pintype "passive"))
      (node (ref "R16") (pin "1") (pinfunction "1_1") (pintype "passive"))
      (node (ref "U7") (pin "4") (pinfunction "4_4") (pintype "passive"))
    )
    (net (code "111") (name "Net-(D6-Pad2)") (class "Default")
      (node (ref "D6") (pin "2") (pinfunction "2_2") (pintype "passive"))
      (node (ref "Q6") (pin "1") (pinfunction "1_1") (pintype "passive"))
      (node (ref "R16") (pin "2") (pinfunction "2_2") (pintype "passive"))
      (node (ref "R22") (pin "2") (pinfunction "2_2") (pintype "passive"))
    )
    (net (code "112") (name "Net-(D7-Pad1)") (class "Default")
      (node (ref "D7") (pin "1") (pinfunction "1_1") (pintype "passive"))
      (node (ref "R19") (pin "1") (pinfunction "1_1") (pintype "passive"))
      (node (ref "U5") (pin "4") (pinfunction "4_4") (pintype "passive"))
    )
    (net (code "113") (name "Net-(D7-Pad2)") (class "Default")
      (node (ref "D7") (pin "2") (pinfunction "2_2") (pintype "passive"))
      (node (ref "Q7") (pin "1") (pinfunction "1_1") (pintype "passive"))
      (node (ref "R19") (pin "2") (pinfunction "2_2") (pintype "passive"))
      (node (ref "R25") (pin "2") (pinfunction "2_2") (pintype "passive"))
    )
    (net (code "114") (name "Net-(D8-Pad1)") (class "Default")
      (node (ref "D8") (pin "1") (pinfunction "1_1") (pintype "passive"))
      (node (ref "R20") (pin "1") (pinfunction "1_1") (pintype "passive"))
      (node (ref "U10") (pin "4") (pinfunction "4_4") (pintype "passive"))
    )
    (net (code "115") (name "Net-(D8-Pad2)") (class "Default")
      (node (ref "D8") (pin "2") (pinfunction "2_2") (pintype "passive"))
      (node (ref "Q8") (pin "1") (pinfunction "1_1") (pintype "passive"))
      (node (ref "R20") (pin "2") (pinfunction "2_2") (pintype "passive"))
      (node (ref "R26") (pin "2") (pinfunction "2_2") (pintype "passive"))
    )
    (net (code "116") (name "Net-(D9-Pad1)") (class "Default")
      (node (ref "D9") (pin "1") (pinfunction "1_1") (pintype "passive"))
      (node (ref "R30") (pin "1") (pinfunction "1_1") (pintype "passive"))
      (node (ref "U9") (pin "4") (pinfunction "4_4") (pintype "passive"))
    )
    (net (code "117") (name "Net-(D9-Pad2)") (class "Default")
      (node (ref "D9") (pin "2") (pinfunction "2_2") (pintype "passive"))
      (node (ref "Q10") (pin "1") (pinfunction "1_1") (pintype "passive"))
      (node (ref "R30") (pin "2") (pinfunction "2_2") (pintype "passive"))
      (node (ref "R46") (pin "2") (pinfunction "2_2") (pintype "passive"))
    )
    (net (code "118") (name "Net-(D10-Pad1)") (class "Default")
      (node (ref "D10") (pin "1") (pinfunction "1_1") (pintype "passive"))
      (node (ref "R29") (pin "1") (pinfunction "1_1") (pintype "passive"))
      (node (ref "U8") (pin "4") (pinfunction "4_4") (pintype "passive"))
    )
    (net (code "119") (name "Net-(D10-Pad2)") (class "Default")
      (node (ref "D10") (pin "2") (pinfunction "2_2") (pintype "passive"))
      (node (ref "Q9") (pin "1") (pinfunction "1_1") (pintype "passive"))
      (node (ref "R29") (pin "2") (pinfunction "2_2") (pintype "passive"))
      (node (ref "R45") (pin "2") (pinfunction "2_2") (pintype "passive"))
    )
    (net (code "120") (name "Net-(D11-Pad1)") (class "Default")
      (node (ref "D11") (pin "1") (pinfunction "1_1") (pintype "passive"))
      (node (ref "R34") (pin "1") (pinfunction "1_1") (pintype "passive"))
      (node (ref "U13") (pin "4") (pinfunction "4_4") (pintype "passive"))
    )
    (net (code "121") (name "Net-(D11-Pad2)") (class "Default")
      (node (ref "D11") (pin "2") (pinfunction "2_2") (pintype "passive"))
      (node (ref "Q12") (pin "1") (pinfunction "1_1") (pintype "passive"))
      (node (ref "R34") (pin "2") (pinfunction "2_2") (pintype "passive"))
      (node (ref "R48") (pin "2") (pinfunction "2_2") (pintype "passive"))
    )
    (net (code "122") (name "Net-(D12-Pad1)") (class "Default")
      (node (ref "D12") (pin "1") (pinfunction "1_1") (pintype "passive"))
      (node (ref "R33") (pin "1") (pinfunction "1_1") (pintype "passive"))
      (node (ref "U12") (pin "4") (pinfunction "4_4") (pintype "passive"))
    )
    (net (code "123") (name "Net-(D12-Pad2)") (class "Default")
      (node (ref "D12") (pin "2") (pinfunction "2_2") (pintype "passive"))
      (node (ref "Q11") (pin "1") (pinfunction "1_1") (pintype "passive"))
      (node (ref "R33") (pin "2") (pinfunction "2_2") (pintype "passive"))
      (node (ref "R47") (pin "2") (pinfunction "2_2") (pintype "passive"))
    )
    (net (code "124") (name "Net-(D13-Pad1)") (class "Default")
      (node (ref "D13") (pin "1") (pinfunction "1_1") (pintype "passive"))
      (node (ref "R35") (pin "1") (pinfunction "1_1") (pintype "passive"))
      (node (ref "U11") (pin "4") (pinfunction "4_4") (pintype "passive"))
    )
    (net (code "125") (name "Net-(D13-Pad2)") (class "Default")
      (node (ref "D13") (pin "2") (pinfunction "2_2") (pintype "passive"))
      (node (ref "Q13") (pin "1") (pinfunction "1_1") (pintype "passive"))
      (node (ref "R35") (pin "2") (pinfunction "2_2") (pintype "passive"))
      (node (ref "R37") (pin "2") (pinfunction "2_2") (pintype "passive"))
    )
    (net (code "126") (name "Net-(D14-Pad1)") (class "Default")
      (node (ref "D14") (pin "1") (pinfunction "1_1") (pintype "passive"))
      (node (ref "R36") (pin "1") (pinfunction "1_1") (pintype "passive"))
      (node (ref "U16") (pin "4") (pinfunction "4_4") (pintype "passive"))
    )
    (net (code "127") (name "Net-(D14-Pad2)") (class "Default")
      (node (ref "D14") (pin "2") (pinfunction "2_2") (pintype "passive"))
      (node (ref "Q14") (pin "1") (pinfunction "1_1") (pintype "passive"))
      (node (ref "R36") (pin "2") (pinfunction "2_2") (pintype "passive"))
      (node (ref "R38") (pin "2") (pinfunction "2_2") (pintype "passive"))
    )
    (net (code "128") (name "Net-(D15-Pad1)") (class "Default")
      (node (ref "D15") (pin "1") (pinfunction "1_1") (pintype "passive"))
      (node (ref "R54") (pin "1") (pinfunction "1_1") (pintype "passive"))
      (node (ref "U15") (pin "4") (pinfunction "4_4") (pintype "passive"))
    )
    (net (code "129") (name "Net-(D15-Pad2)") (class "Default")
      (node (ref "D15") (pin "2") (pinfunction "2_2") (pintype "passive"))
      (node (ref "Q18") (pin "1") (pinfunction "1_1") (pintype "passive"))
      (node (ref "R54") (pin "2") (pinfunction "2_2") (pintype "passive"))
      (node (ref "R57") (pin "2") (pinfunction "2_2") (pintype "passive"))
    )
    (net (code "130") (name "Net-(D16-Pad1)") (class "Default")
      (node (ref "D16") (pin "1") (pinfunction "1_1") (pintype "passive"))
      (node (ref "R56") (pin "1") (pinfunction "1_1") (pintype "passive"))
      (node (ref "U20") (pin "4") (pinfunction "4_4") (pintype "passive"))
    )
    (net (code "131") (name "Net-(D16-Pad2)") (class "Default")
      (node (ref "D16") (pin "2") (pinfunction "2_2") (pintype "passive"))
      (node (ref "Q20") (pin "1") (pinfunction "1_1") (pintype "passive"))
      (node (ref "R56") (pin "2") (pinfunction "2_2") (pintype "passive"))
      (node (ref "R59") (pin "2") (pinfunction "2_2") (pintype "passive"))
    )
    (net (code "132") (name "Net-(D17-Pad1)") (class "Default")
      (node (ref "D17") (pin "1") (pinfunction "1_1") (pintype "passive"))
      (node (ref "R53") (pin "1") (pinfunction "1_1") (pintype "passive"))
      (node (ref "U14") (pin "4") (pinfunction "4_4") (pintype "passive"))
    )
    (net (code "133") (name "Net-(D17-Pad2)") (class "Default")
      (node (ref "D17") (pin "2") (pinfunction "2_2") (pintype "passive"))
      (node (ref "Q17") (pin "1") (pinfunction "1_1") (pintype "passive"))
      (node (ref "R53") (pin "2") (pinfunction "2_2") (pintype "passive"))
      (node (ref "R58") (pin "2") (pinfunction "2_2") (pintype "passive"))
    )
    (net (code "134") (name "Net-(D18-Pad1)") (class "Default")
      (node (ref "D18") (pin "1") (pinfunction "1_1") (pintype "passive"))
      (node (ref "R55") (pin "1") (pinfunction "1_1") (pintype "passive"))
      (node (ref "U19") (pin "4") (pinfunction "4_4") (pintype "passive"))
    )
    (net (code "135") (name "Net-(D18-Pad2)") (class "Default")
      (node (ref "D18") (pin "2") (pinfunction "2_2") (pintype "passive"))
      (node (ref "Q19") (pin "1") (pinfunction "1_1") (pintype "passive"))
      (node (ref "R55") (pin "2") (pinfunction "2_2") (pintype "passive"))
      (node (ref "R60") (pin "2") (pinfunction "2_2") (pintype "passive"))
    )
    (net (code "136") (name "Net-(D19-Pad1)") (class "Default")
      (node (ref "D19") (pin "1") (pinfunction "1_1") (pintype "passive"))
      (node (ref "R41") (pin "1") (pinfunction "1_1") (pintype "passive"))
      (node (ref "U17") (pin "4") (pinfunction "4_4") (pintype "passive"))
    )
    (net (code "137") (name "Net-(D19-Pad2)") (class "Default")
      (node (ref "D19") (pin "2") (pinfunction "2_2") (pintype "passive"))
      (node (ref "Q15") (pin "1") (pinfunction "1_1") (pintype "passive"))
      (node (ref "R41") (pin "2") (pinfunction "2_2") (pintype "passive"))
      (node (ref "R43") (pin "2") (pinfunction "2_2") (pintype "passive"))
    )
    (net (code "138") (name "Net-(D20-Pad1)") (class "Default")
      (node (ref "D20") (pin "1") (pinfunction "1_1") (pintype "passive"))
      (node (ref "R42") (pin "1") (pinfunction "1_1") (pintype "passive"))
      (node (ref "U18") (pin "4") (pinfunction "4_4") (pintype "passive"))
    )
    (net (code "139") (name "Net-(D20-Pad2)") (class "Default")
      (node (ref "D20") (pin "2") (pinfunction "2_2") (pintype "passive"))
      (node (ref "Q16") (pin "1") (pinfunction "1_1") (pintype "passive"))
      (node (ref "R42") (pin "2") (pinfunction "2_2") (pintype "passive"))
      (node (ref "R44") (pin "2") (pinfunction "2_2") (pintype "passive"))
    )
    (net (code "140") (name "Net-(D21-Pad1)") (class "Default")
      (node (ref "D21") (pin "1") (pinfunction "1_1") (pintype "passive"))
      (node (ref "R65") (pin "1") (pinfunction "1_1") (pintype "passive"))
      (node (ref "U21") (pin "4") (pinfunction "4_4") (pintype "passive"))
    )
    (net (code "141") (name "Net-(D21-Pad2)") (class "Default")
      (node (ref "D21") (pin "2") (pinfunction "2_2") (pintype "passive"))
      (node (ref "Q21") (pin "1") (pinfunction "1_1") (pintype "passive"))
      (node (ref "R65") (pin "2") (pinfunction "2_2") (pintype "passive"))
      (node (ref "R69") (pin "2") (pinfunction "2_2") (pintype "passive"))
    )
    (net (code "142") (name "Net-(D22-Pad1)") (class "Default")
      (node (ref "D22") (pin "1") (pinfunction "1_1") (pintype "passive"))
      (node (ref "R67") (pin "1") (pinfunction "1_1") (pintype "passive"))
      (node (ref "U23") (pin "4") (pinfunction "4_4") (pintype "passive"))
    )
    (net (code "143") (name "Net-(D22-Pad2)") (class "Default")
      (node (ref "D22") (pin "2") (pinfunction "2_2") (pintype "passive"))
      (node (ref "Q23") (pin "1") (pinfunction "1_1") (pintype "passive"))
      (node (ref "R67") (pin "2") (pinfunction "2_2") (pintype "passive"))
      (node (ref "R71") (pin "2") (pinfunction "2_2") (pintype "passive"))
    )
    (net (code "144") (name "Net-(D23-Pad1)") (class "Default")
      (node (ref "D23") (pin "1") (pinfunction "1_1") (pintype "passive"))
      (node (ref "R66") (pin "1") (pinfunction "1_1") (pintype "passive"))
      (node (ref "U22") (pin "4") (pinfunction "4_4") (pintype "passive"))
    )
    (net (code "145") (name "Net-(D23-Pad2)") (class "Default")
      (node (ref "D23") (pin "2") (pinfunction "2_2") (pintype "passive"))
      (node (ref "Q22") (pin "1") (pinfunction "1_1") (pintype "passive"))
      (node (ref "R66") (pin "2") (pinfunction "2_2") (pintype "passive"))
      (node (ref "R70") (pin "2") (pinfunction "2_2") (pintype "passive"))
    )
    (net (code "146") (name "Net-(D24-Pad1)") (class "Default")
      (node (ref "D24") (pin "1") (pinfunction "1_1") (pintype "passive"))
      (node (ref "R68") (pin "1") (pinfunction "1_1") (pintype "passive"))
      (node (ref "U24") (pin "4") (pinfunction "4_4") (pintype "passive"))
    )
    (net (code "147") (name "Net-(D24-Pad2)") (class "Default")
      (node (ref "D24") (pin "2") (pinfunction "2_2") (pintype "passive"))
      (node (ref "Q24") (pin "1") (pinfunction "1_1") (pintype "passive"))
      (node (ref "R68") (pin "2") (pinfunction "2_2") (pintype "passive"))
      (node (ref "R72") (pin "2") (pinfunction "2_2") (pintype "passive"))
    )
    (net (code "148") (name "Net-(R1-Pad2)") (class "Default")
      (node (ref "R1") (pin "2") (pinfunction "2_2") (pintype "passive"))
      (node (ref "U1") (pin "1") (pinfunction "1_1") (pintype "passive"))
    )
    (net (code "149") (name "Net-(R2-Pad2)") (class "Default")
      (node (ref "R2") (pin "2") (pinfunction "2_2") (pintype "passive"))
      (node (ref "U4") (pin "1") (pinfunction "1_1") (pintype "passive"))
    )
    (net (code "150") (name "Net-(R7-Pad2)") (class "Default")
      (node (ref "R7") (pin "2") (pinfunction "2_2") (pintype "passive"))
      (node (ref "U5") (pin "1") (pinfunction "1_1") (pintype "passive"))
    )
    (net (code "151") (name "Net-(R8-Pad2)") (class "Default")
      (node (ref "R8") (pin "2") (pinfunction "2_2") (pintype "passive"))
      (node (ref "U10") (pin "1") (pinfunction "1_1") (pintype "passive"))
    )
    (net (code "152") (name "Net-(R9-Pad2)") (class "Default")
      (node (ref "R9") (pin "2") (pinfunction "2_2") (pintype "passive"))
      (node (ref "U2") (pin "1") (pinfunction "1_1") (pintype "passive"))
    )
    (net (code "153") (name "Net-(R10-Pad2)") (class "Default")
      (node (ref "R10") (pin "2") (pinfunction "2_2") (pintype "passive"))
      (node (ref "U3") (pin "1") (pinfunction "1_1") (pintype "passive"))
    )
    (net (code "154") (name "Net-(R11-Pad2)") (class "Default")
      (node (ref "R11") (pin "2") (pinfunction "2_2") (pintype "passive"))
      (node (ref "U6") (pin "1") (pinfunction "1_1") (pintype "passive"))
    )
    (net (code "155") (name "Net-(R12-Pad2)") (class "Default")
      (node (ref "R12") (pin "2") (pinfunction "2_2") (pintype "passive"))
      (node (ref "U7") (pin "1") (pinfunction "1_1") (pintype "passive"))
    )
    (net (code "156") (name "Net-(R23-Pad2)") (class "Default")
      (node (ref "R23") (pin "2") (pinfunction "2_2") (pintype "passive"))
      (node (ref "U8") (pin "1") (pinfunction "1_1") (pintype "passive"))
    )
    (net (code "157") (name "Net-(R24-Pad2)") (class "Default")
      (node (ref "R24") (pin "2") (pinfunction "2_2") (pintype "passive"))
      (node (ref "U9") (pin "1") (pinfunction "1_1") (pintype "passive"))
    )
    (net (code "158") (name "Net-(R27-Pad2)") (class "Default")
      (node (ref "R27") (pin "2") (pinfunction "2_2") (pintype "passive"))
      (node (ref "U12") (pin "1") (pinfunction "1_1") (pintype "passive"))
    )
    (net (code "159") (name "Net-(R28-Pad2)") (class "Default")
      (node (ref "R28") (pin "2") (pinfunction "2_2") (pintype "passive"))
      (node (ref "U13") (pin "1") (pinfunction "1_1") (pintype "passive"))
    )
    (net (code "160") (name "Net-(R31-Pad2)") (class "Default")
      (node (ref "R31") (pin "2") (pinfunction "2_2") (pintype "passive"))
      (node (ref "U11") (pin "1") (pinfunction "1_1") (pintype "passive"))
    )
    (net (code "161") (name "Net-(R32-Pad2)") (class "Default")
      (node (ref "R32") (pin "2") (pinfunction "2_2") (pintype "passive"))
      (node (ref "U16") (pin "1") (pinfunction "1_1") (pintype "passive"))
    )
    (net (code "162") (name "Net-(R39-Pad2)") (class "Default")
      (node (ref "R39") (pin "2") (pinfunction "2_2") (pintype "passive"))
      (node (ref "U17") (pin "1") (pinfunction "1_1") (pintype "passive"))
    )
    (net (code "163") (name "Net-(R40-Pad2)") (class "Default")
      (node (ref "R40") (pin "2") (pinfunction "2_2") (pintype "passive"))
      (node (ref "U18") (pin "1") (pinfunction "1_1") (pintype "passive"))
    )
    (net (code "164") (name "Net-(R49-Pad2)") (class "Default")
      (node (ref "R49") (pin "2") (pinfunction "2_2") (pintype "passive"))
      (node (ref "U14") (pin "1") (pinfunction "1_1") (pintype "passive"))
    )
    (net (code "165") (name "Net-(R50-Pad2)") (class "Default")
      (node (ref "R50") (pin "2") (pinfunction "2_2") (pintype "passive"))
      (node (ref "U15") (pin "1") (pinfunction "1_1") (pintype "passive"))
    )
    (net (code "166") (name "Net-(R51-Pad2)") (class "Default")
      (node (ref "R51") (pin "2") (pinfunction "2_2") (pintype "passive"))
      (node (ref "U19") (pin "1") (pinfunction "1_1") (pintype "passive"))
    )
    (net (code "167") (name "Net-(R52-Pad2)") (class "Default")
      (node (ref "R52") (pin "2") (pinfunction "2_2") (pintype "passive"))
      (node (ref "U20") (pin "1") (pinfunction "1_1") (pintype "passive"))
    )
    (net (code "168") (name "Net-(R61-Pad2)") (class "Default")
      (node (ref "R61") (pin "2") (pinfunction "2_2") (pintype "passive"))
      (node (ref "U21") (pin "1") (pinfunction "1_1") (pintype "passive"))
    )
    (net (code "169") (name "Net-(R62-Pad2)") (class "Default")
      (node (ref "R62") (pin "2") (pinfunction "2_2") (pintype "passive"))
      (node (ref "U22") (pin "1") (pinfunction "1_1") (pintype "passive"))
    )
    (net (code "170") (name "Net-(R63-Pad2)") (class "Default")
      (node (ref "R63") (pin "2") (pinfunction "2_2") (pintype "passive"))
      (node (ref "U23") (pin "1") (pinfunction "1_1") (pintype "passive"))
    )
    (net (code "171") (name "Net-(R64-Pad2)") (class "Default")
      (node (ref "R64") (pin "2") (pinfunction "2_2") (pintype "passive"))
      (node (ref "U24") (pin "1") (pinfunction "1_1") (pintype "passive"))
    )
    (net (code "172") (name "Neutral") (class "Default")
      (node (ref "Q14") (pin "3") (pinfunction "3_3") (pintype "passive"))
      (node (ref "Q16") (pin "2") (pinfunction "2_2") (pintype "passive"))
      (node (ref "Q18") (pin "3") (pinfunction "3_3") (pintype "passive"))
      (node (ref "Q20") (pin "3") (pinfunction "3_3") (pintype "passive"))
      (node (ref "Q22") (pin "2") (pinfunction "2_2") (pintype "passive"))
      (node (ref "Q24") (pin "2") (pinfunction "2_2") (pintype "passive"))
      (node (ref "R38") (pin "1") (pinfunction "1_1") (pintype "passive"))
      (node (ref "R57") (pin "1") (pinfunction "1_1") (pintype "passive"))
      (node (ref "R59") (pin "1") (pinfunction "1_1") (pintype "passive"))
      (node (ref "X14") (pin "6") (pinfunction "6_6") (pintype "passive"))
      (node (ref "X17") (pin "6") (pinfunction "6_6") (pintype "passive"))
      (node (ref "X4") (pin "6") (pinfunction "6_6") (pintype "passive"))
    )
    (net (code "173") (name "PhaseA") (class "Default")
      (node (ref "Q1") (pin "3") (pinfunction "3_3") (pintype "passive"))
      (node (ref "Q7") (pin "2") (pinfunction "2_2") (pintype "passive"))
      (node (ref "R5") (pin "1") (pinfunction "1_1") (pintype "passive"))
      (node (ref "X1") (pin "6") (pinfunction "6_6") (pintype "passive"))
    )
    (net (code "174") (name "PhaseB") (class "Default")
      (node (ref "Q3") (pin "3") (pinfunction "3_3") (pintype "passive"))
      (node (ref "Q9") (pin "2") (pinfunction "2_2") (pintype "passive"))
      (node (ref "R17") (pin "1") (pinfunction "1_1") (pintype "passive"))
      (node (ref "X8") (pin "6") (pinfunction "6_6") (pintype "passive"))
    )
    (net (code "175") (name "PhaseC") (class "Default")
      (node (ref "Q11") (pin "2") (pinfunction "2_2") (pintype "passive"))
      (node (ref "Q5") (pin "3") (pinfunction "3_3") (pintype "passive"))
      (node (ref "R21") (pin "1") (pinfunction "1_1") (pintype "passive"))
      (node (ref "X11") (pin "6") (pinfunction "6_6") (pintype "passive"))
    )
  )
)
